# WT_ControlBoardV2.net
KiCad netlist of a schematic drawn in EAGLE
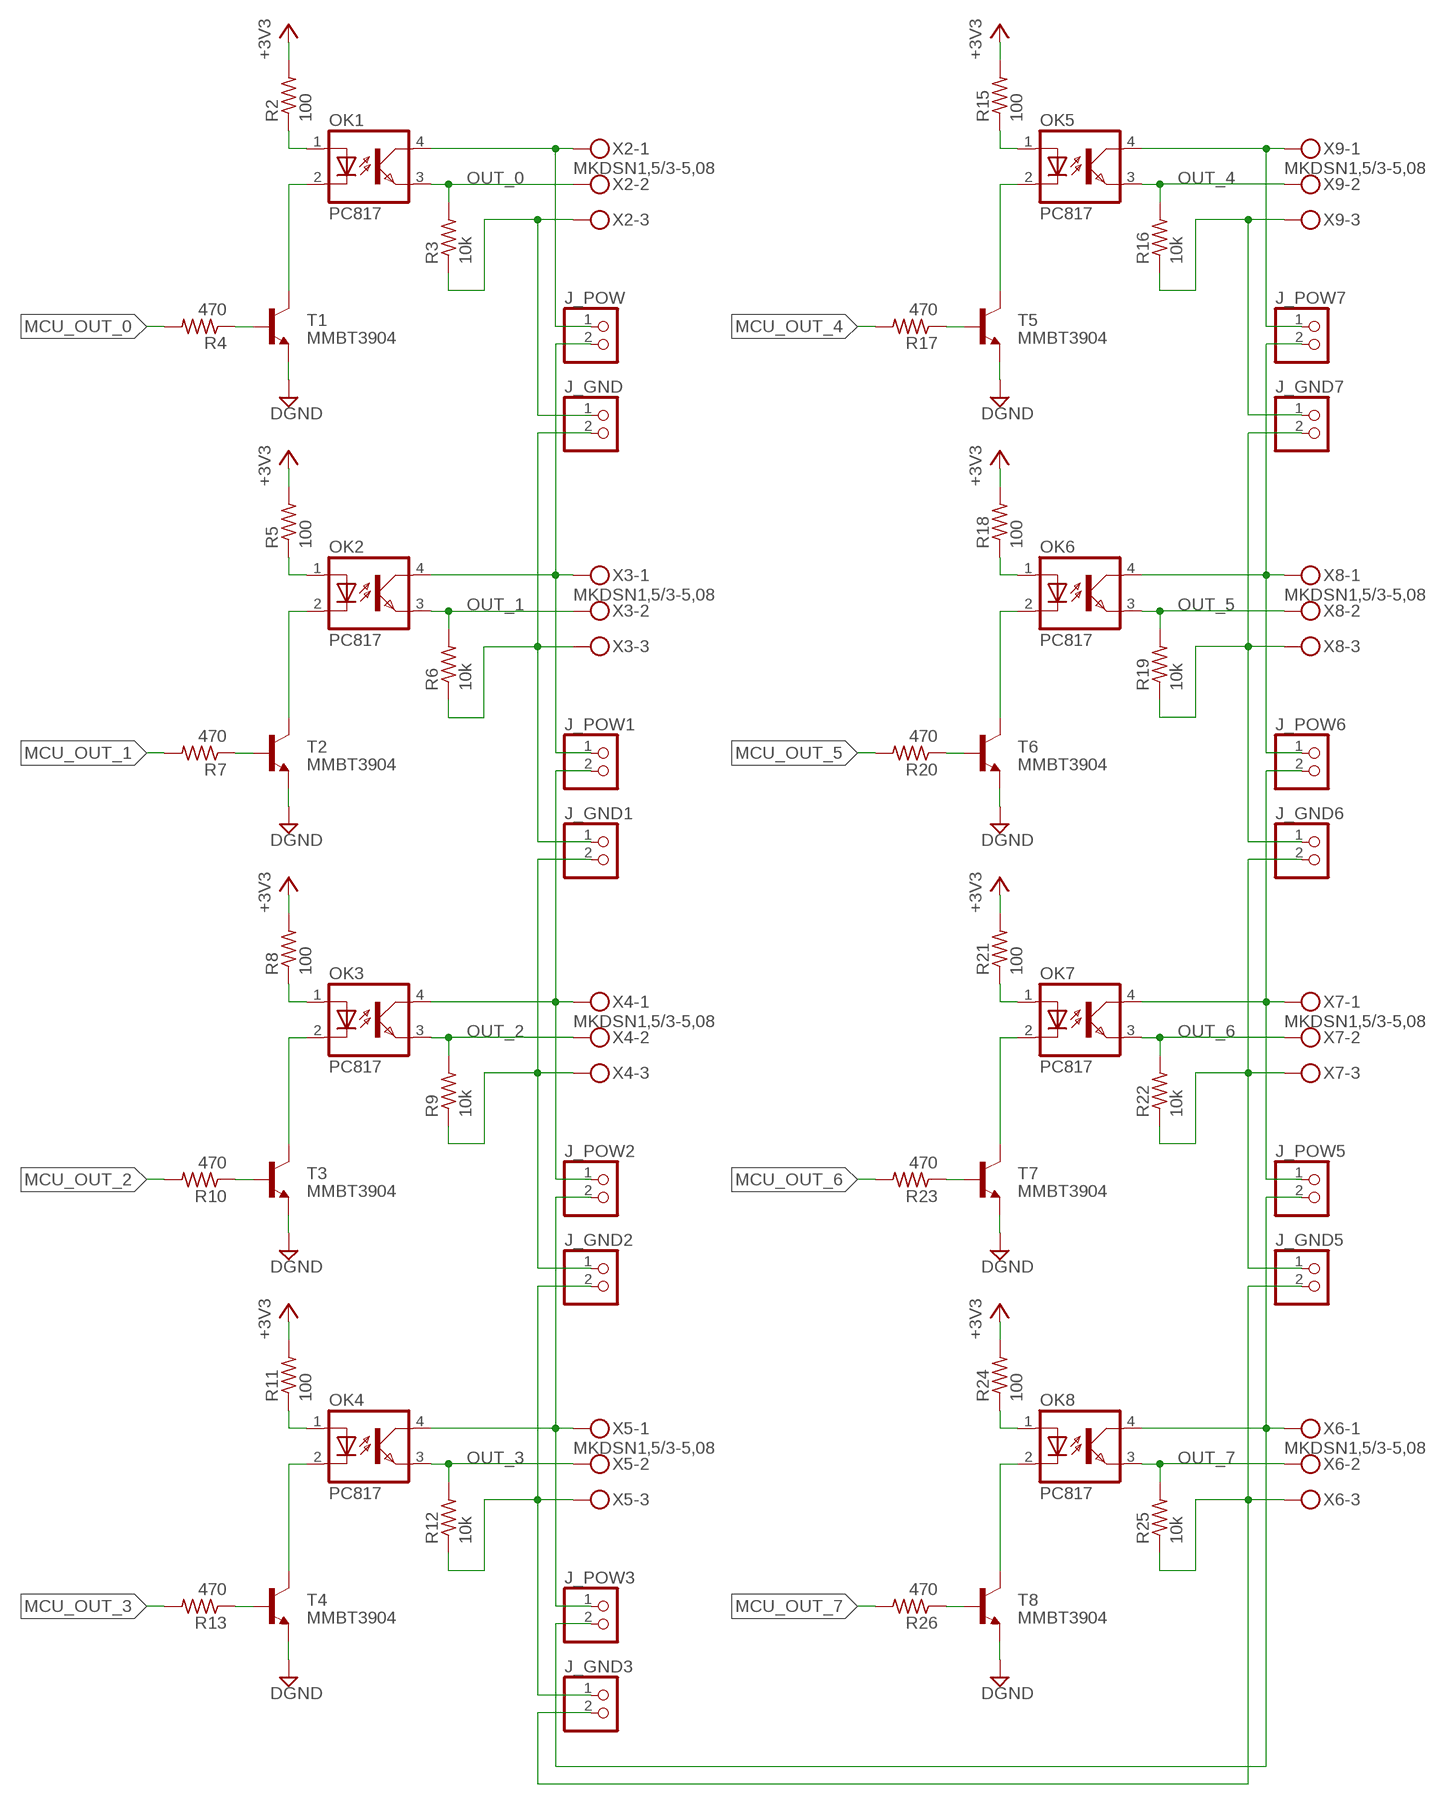
[diagram p0: schematic, sheet 1]
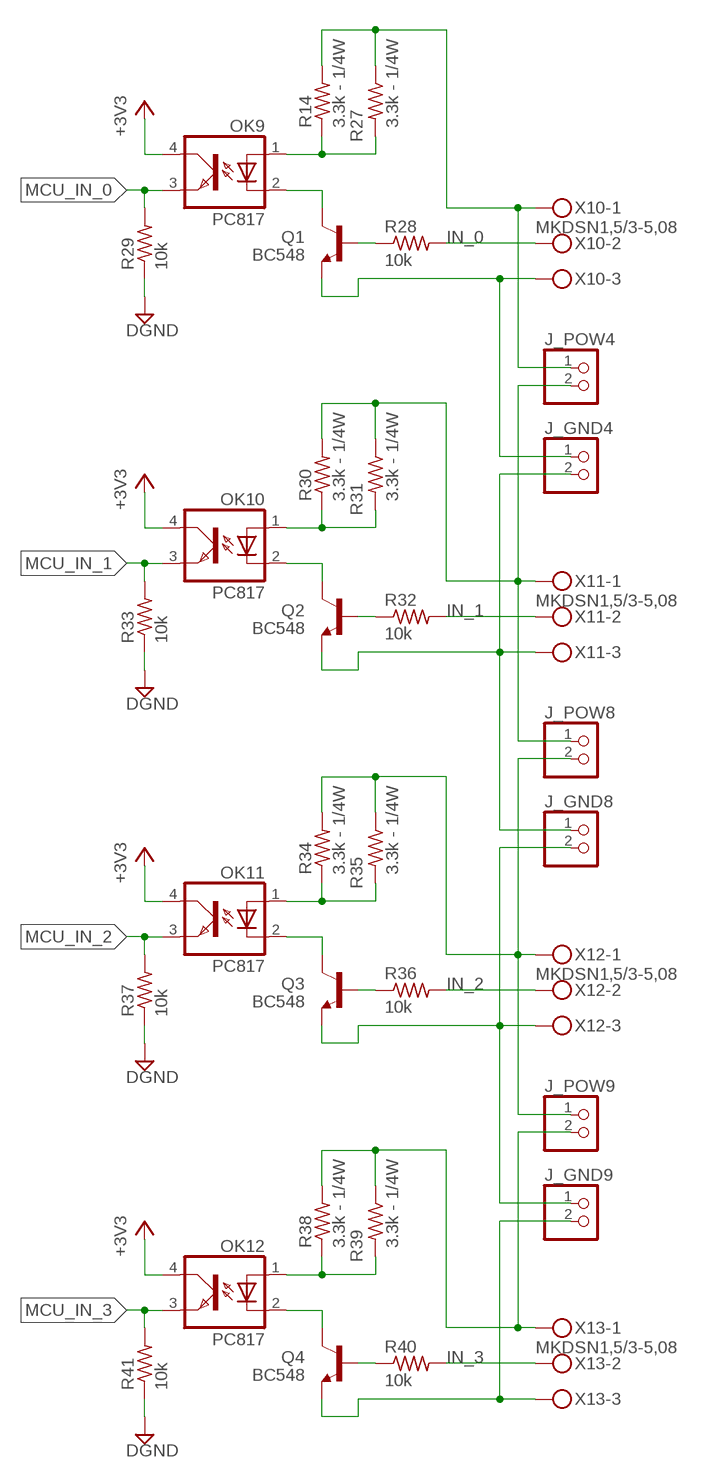
[diagram p1: schematic, sheet 2]
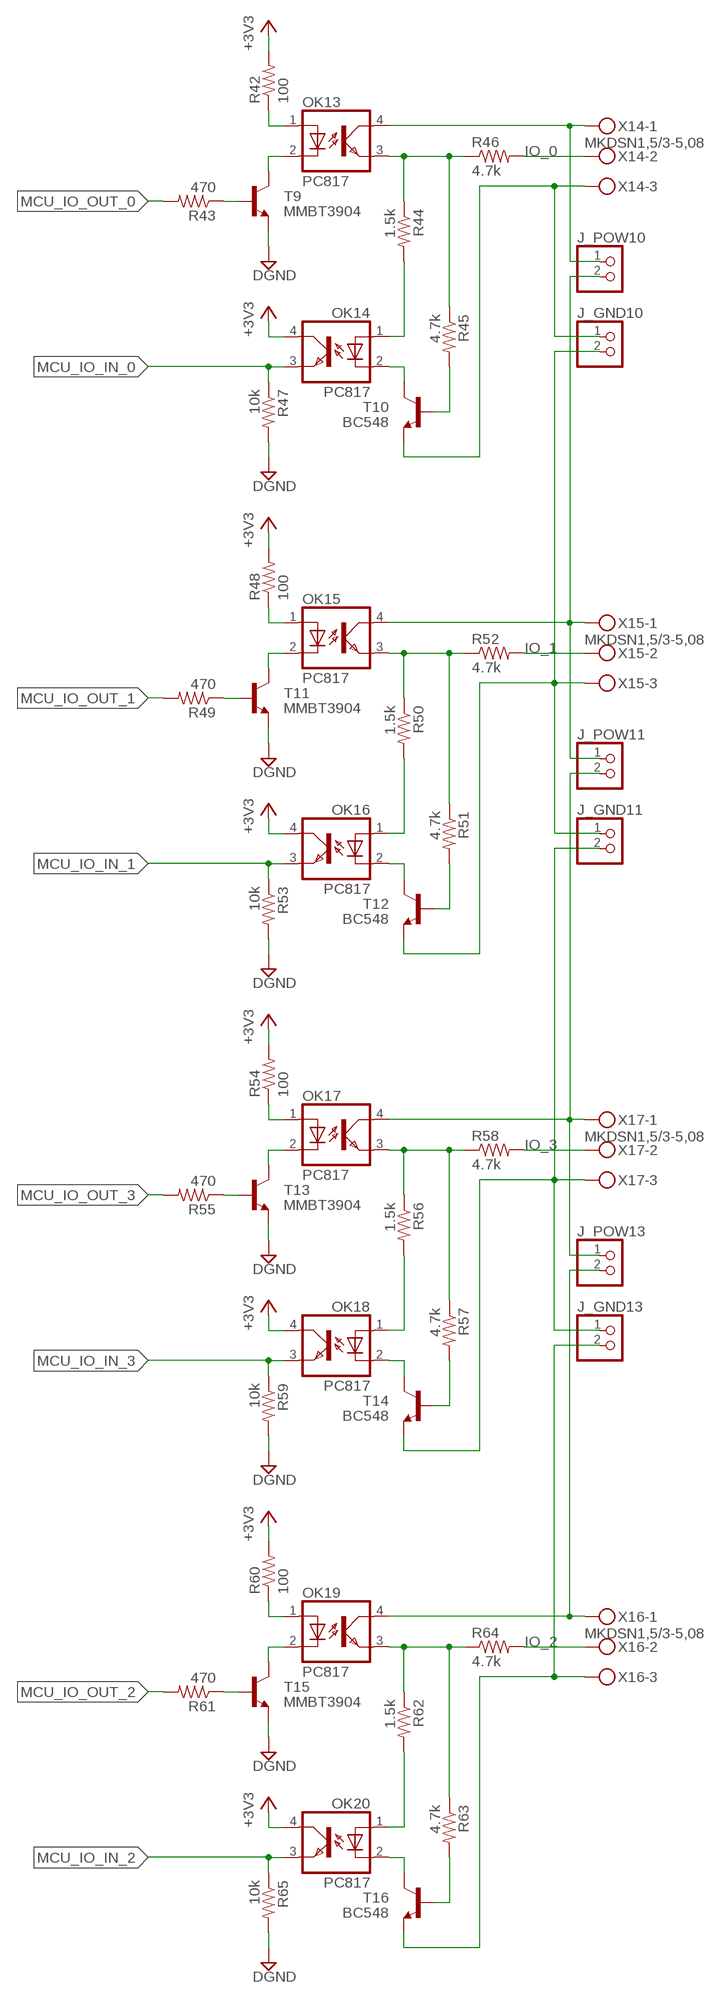
[diagram p2: schematic, sheet 3]
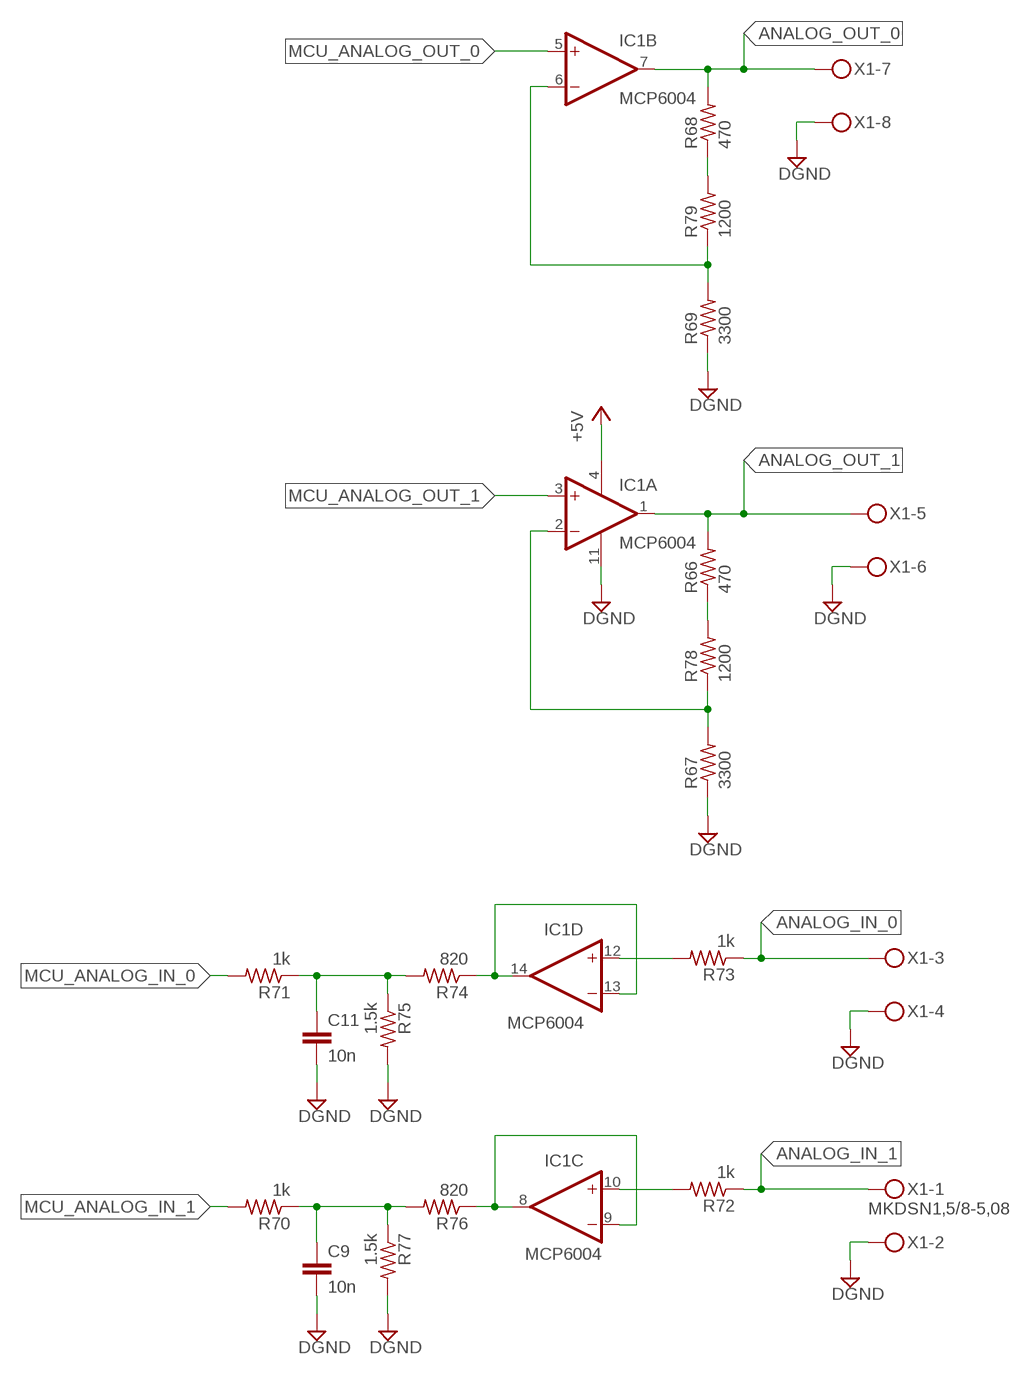
[diagram p3: schematic, sheet 4]
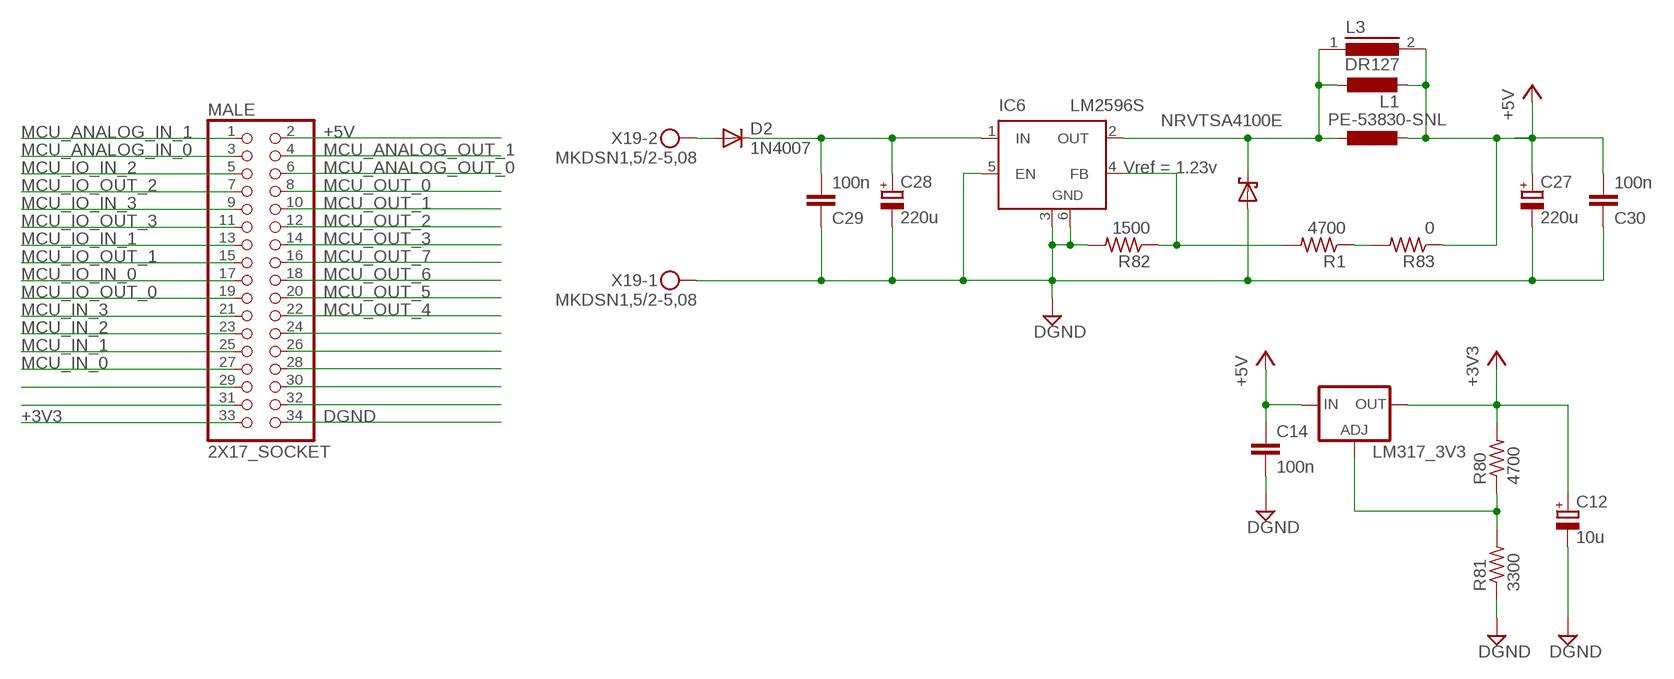
[diagram p4: schematic, sheet 5]

(export (version "E")
  (design (tool "Eeschema 10.0.6"))
  (components
    (comp (ref "J_GND4")
      (value "PINHD-1X2")
      (footprint "eagle-import:1X02")
      (libsource (lib "eagle-import") (part "PINHD-1X2"))
    )
    (comp (ref "J_GND8")
      (value "PINHD-1X2")
      (footprint "eagle-import:1X02")
      (libsource (lib "eagle-import") (part "PINHD-1X2"))
    )
    (comp (ref "J_GND9")
      (value "PINHD-1X2")
      (footprint "eagle-import:1X02")
      (libsource (lib "eagle-import") (part "PINHD-1X2"))
    )
    (comp (ref "J_POW4")
      (value "PINHD-1X2")
      (footprint "eagle-import:1X02")
      (libsource (lib "eagle-import") (part "PINHD-1X2"))
    )
    (comp (ref "J_POW8")
      (value "PINHD-1X2")
      (footprint "eagle-import:1X02")
      (libsource (lib "eagle-import") (part "PINHD-1X2"))
    )
    (comp (ref "J_POW9")
      (value "PINHD-1X2")
      (footprint "eagle-import:1X02")
      (libsource (lib "eagle-import") (part "PINHD-1X2"))
    )
    (comp (ref "OK9")
      (value "PC817")
      (footprint "eagle-import:DIL04")
      (fields (field (name "MPN") "PC817X4J000F"))
      (libsource (lib "eagle-import") (part "PC817"))
    )
    (comp (ref "OK10")
      (value "PC817")
      (footprint "eagle-import:DIL04")
      (fields (field (name "MPN") "PC817X4J000F"))
      (libsource (lib "eagle-import") (part "PC817"))
    )
    (comp (ref "OK11")
      (value "PC817")
      (footprint "eagle-import:DIL04")
      (fields (field (name "MPN") "PC817X4J000F"))
      (libsource (lib "eagle-import") (part "PC817"))
    )
    (comp (ref "OK12")
      (value "PC817")
      (footprint "eagle-import:DIL04")
      (fields (field (name "MPN") "PC817X4J000F"))
      (libsource (lib "eagle-import") (part "PC817"))
    )
    (comp (ref "Q1")
      (value "BC548")
      (footprint "eagle-import:TO92-EBC")
      (libsource (lib "eagle-import") (part "BC548"))
    )
    (comp (ref "Q2")
      (value "BC548")
      (footprint "eagle-import:TO92-EBC")
      (libsource (lib "eagle-import") (part "BC548"))
    )
    (comp (ref "Q3")
      (value "BC548")
      (footprint "eagle-import:TO92-EBC")
      (libsource (lib "eagle-import") (part "BC548"))
    )
    (comp (ref "Q4")
      (value "BC548")
      (footprint "eagle-import:TO92-EBC")
      (libsource (lib "eagle-import") (part "BC548"))
    )
    (comp (ref "R14")
      (value "3.3k - 1/4W")
      (footprint "eagle-import:0204V")
      (libsource (lib "eagle-import") (part "R-US_0204/2V"))
    )
    (comp (ref "R27")
      (value "3.3k - 1/4W")
      (footprint "eagle-import:0204V")
      (libsource (lib "eagle-import") (part "R-US_0204/2V"))
    )
    (comp (ref "R28")
      (value "10k")
      (footprint "eagle-import:0204_5")
      (libsource (lib "eagle-import") (part "R-US_0204/5"))
    )
    (comp (ref "R29")
      (value "10k")
      (footprint "eagle-import:R0402")
      (libsource (lib "eagle-import") (part "R-US_R0402"))
    )
    (comp (ref "R30")
      (value "3.3k - 1/4W")
      (footprint "eagle-import:0204V")
      (libsource (lib "eagle-import") (part "R-US_0204/2V"))
    )
    (comp (ref "R31")
      (value "3.3k - 1/4W")
      (footprint "eagle-import:0204V")
      (libsource (lib "eagle-import") (part "R-US_0204/2V"))
    )
    (comp (ref "R32")
      (value "10k")
      (footprint "eagle-import:0204_5")
      (libsource (lib "eagle-import") (part "R-US_0204/5"))
    )
    (comp (ref "R33")
      (value "10k")
      (footprint "eagle-import:R0402")
      (libsource (lib "eagle-import") (part "R-US_R0402"))
    )
    (comp (ref "R34")
      (value "3.3k - 1/4W")
      (footprint "eagle-import:0204V")
      (libsource (lib "eagle-import") (part "R-US_0204/2V"))
    )
    (comp (ref "R35")
      (value "3.3k - 1/4W")
      (footprint "eagle-import:0204V")
      (libsource (lib "eagle-import") (part "R-US_0204/2V"))
    )
    (comp (ref "R36")
      (value "10k")
      (footprint "eagle-import:0204_5")
      (libsource (lib "eagle-import") (part "R-US_0204/5"))
    )
    (comp (ref "R37")
      (value "10k")
      (footprint "eagle-import:R0402")
      (libsource (lib "eagle-import") (part "R-US_R0402"))
    )
    (comp (ref "R38")
      (value "3.3k - 1/4W")
      (footprint "eagle-import:0204V")
      (libsource (lib "eagle-import") (part "R-US_0204/2V"))
    )
    (comp (ref "R39")
      (value "3.3k - 1/4W")
      (footprint "eagle-import:0204V")
      (libsource (lib "eagle-import") (part "R-US_0204/2V"))
    )
    (comp (ref "R40")
      (value "10k")
      (footprint "eagle-import:0204_5")
      (libsource (lib "eagle-import") (part "R-US_0204/5"))
    )
    (comp (ref "R41")
      (value "10k")
      (footprint "eagle-import:R0402")
      (libsource (lib "eagle-import") (part "R-US_R0402"))
    )
    (comp (ref "X10")
      (value "MKDSN1,5/3-5,08")
      (footprint "eagle-import:MKDSN1,5_3-5,08")
      (libsource (lib "eagle-import") (part "MKDSN1,5/3-5,08"))
    )
    (comp (ref "X11")
      (value "MKDSN1,5/3-5,08")
      (footprint "eagle-import:MKDSN1,5_3-5,08")
      (libsource (lib "eagle-import") (part "MKDSN1,5/3-5,08"))
    )
    (comp (ref "X12")
      (value "MKDSN1,5/3-5,08")
      (footprint "eagle-import:MKDSN1,5_3-5,08")
      (libsource (lib "eagle-import") (part "MKDSN1,5/3-5,08"))
    )
    (comp (ref "X13")
      (value "MKDSN1,5/3-5,08")
      (footprint "eagle-import:MKDSN1,5_3-5,08")
      (libsource (lib "eagle-import") (part "MKDSN1,5/3-5,08"))
    )
    (comp (ref "J_GND10")
      (value "PINHD-1X2")
      (footprint "eagle-import:1X02")
      (libsource (lib "eagle-import") (part "PINHD-1X2"))
    )
    (comp (ref "J_GND11")
      (value "PINHD-1X2")
      (footprint "eagle-import:1X02")
      (libsource (lib "eagle-import") (part "PINHD-1X2"))
    )
    (comp (ref "J_GND13")
      (value "PINHD-1X2")
      (footprint "eagle-import:1X02")
      (libsource (lib "eagle-import") (part "PINHD-1X2"))
    )
    (comp (ref "J_POW10")
      (value "PINHD-1X2")
      (footprint "eagle-import:1X02")
      (libsource (lib "eagle-import") (part "PINHD-1X2"))
    )
    (comp (ref "J_POW11")
      (value "PINHD-1X2")
      (footprint "eagle-import:1X02")
      (libsource (lib "eagle-import") (part "PINHD-1X2"))
    )
    (comp (ref "J_POW13")
      (value "PINHD-1X2")
      (footprint "eagle-import:1X02")
      (libsource (lib "eagle-import") (part "PINHD-1X2"))
    )
    (comp (ref "OK13")
      (value "PC817")
      (footprint "eagle-import:DIL04")
      (fields (field (name "MPN") "PC817X4J000F"))
      (libsource (lib "eagle-import") (part "PC817"))
    )
    (comp (ref "OK14")
      (value "PC817")
      (footprint "eagle-import:DIL04")
      (fields (field (name "MPN") "PC817X4J000F"))
      (libsource (lib "eagle-import") (part "PC817"))
    )
    (comp (ref "OK15")
      (value "PC817")
      (footprint "eagle-import:DIL04")
      (fields (field (name "MPN") "PC817X4J000F"))
      (libsource (lib "eagle-import") (part "PC817"))
    )
    (comp (ref "OK16")
      (value "PC817")
      (footprint "eagle-import:DIL04")
      (fields (field (name "MPN") "PC817X4J000F"))
      (libsource (lib "eagle-import") (part "PC817"))
    )
    (comp (ref "OK17")
      (value "PC817")
      (footprint "eagle-import:DIL04")
      (fields (field (name "MPN") "PC817X4J000F"))
      (libsource (lib "eagle-import") (part "PC817"))
    )
    (comp (ref "OK18")
      (value "PC817")
      (footprint "eagle-import:DIL04")
      (fields (field (name "MPN") "PC817X4J000F"))
      (libsource (lib "eagle-import") (part "PC817"))
    )
    (comp (ref "OK19")
      (value "PC817")
      (footprint "eagle-import:DIL04")
      (fields (field (name "MPN") "PC817X4J000F"))
      (libsource (lib "eagle-import") (part "PC817"))
    )
    (comp (ref "OK20")
      (value "PC817")
      (footprint "eagle-import:DIL04")
      (fields (field (name "MPN") "PC817X4J000F"))
      (libsource (lib "eagle-import") (part "PC817"))
    )
    (comp (ref "R42")
      (value "100")
      (footprint "eagle-import:0204_7")
      (libsource (lib "eagle-import") (part "R-US_0204/7"))
    )
    (comp (ref "R43")
      (value "470")
      (footprint "eagle-import:R0402")
      (libsource (lib "eagle-import") (part "R-US_R0402"))
    )
    (comp (ref "R44")
      (value "1.5k")
      (footprint "eagle-import:0204_5")
      (libsource (lib "eagle-import") (part "R-US_0204/5"))
    )
    (comp (ref "R45")
      (value "4.7k")
      (footprint "eagle-import:0204V")
      (libsource (lib "eagle-import") (part "R-US_0204/2V"))
    )
    (comp (ref "R46")
      (value "4.7k")
      (footprint "eagle-import:0204V")
      (libsource (lib "eagle-import") (part "R-US_0204/2V"))
    )
    (comp (ref "R47")
      (value "10k")
      (footprint "eagle-import:0204_5")
      (libsource (lib "eagle-import") (part "R-US_0204/5"))
    )
    (comp (ref "R48")
      (value "100")
      (footprint "eagle-import:0204_7")
      (libsource (lib "eagle-import") (part "R-US_0204/7"))
    )
    (comp (ref "R49")
      (value "470")
      (footprint "eagle-import:R0402")
      (libsource (lib "eagle-import") (part "R-US_R0402"))
    )
    (comp (ref "R50")
      (value "1.5k")
      (footprint "eagle-import:0204_5")
      (libsource (lib "eagle-import") (part "R-US_0204/5"))
    )
    (comp (ref "R51")
      (value "4.7k")
      (footprint "eagle-import:0204V")
      (libsource (lib "eagle-import") (part "R-US_0204/2V"))
    )
    (comp (ref "R52")
      (value "4.7k")
      (footprint "eagle-import:0204V")
      (libsource (lib "eagle-import") (part "R-US_0204/2V"))
    )
    (comp (ref "R53")
      (value "10k")
      (footprint "eagle-import:0204_5")
      (libsource (lib "eagle-import") (part "R-US_0204/5"))
    )
    (comp (ref "R54")
      (value "100")
      (footprint "eagle-import:0204_7")
      (libsource (lib "eagle-import") (part "R-US_0204/7"))
    )
    (comp (ref "R55")
      (value "470")
      (footprint "eagle-import:R0402")
      (libsource (lib "eagle-import") (part "R-US_R0402"))
    )
    (comp (ref "R56")
      (value "1.5k")
      (footprint "eagle-import:0204_5")
      (libsource (lib "eagle-import") (part "R-US_0204/5"))
    )
    (comp (ref "R57")
      (value "4.7k")
      (footprint "eagle-import:0204V")
      (libsource (lib "eagle-import") (part "R-US_0204/2V"))
    )
    (comp (ref "R58")
      (value "4.7k")
      (footprint "eagle-import:0204V")
      (libsource (lib "eagle-import") (part "R-US_0204/2V"))
    )
    (comp (ref "R59")
      (value "10k")
      (footprint "eagle-import:0204_5")
      (libsource (lib "eagle-import") (part "R-US_0204/5"))
    )
    (comp (ref "R60")
      (value "100")
      (footprint "eagle-import:0204_7")
      (libsource (lib "eagle-import") (part "R-US_0204/7"))
    )
    (comp (ref "R61")
      (value "470")
      (footprint "eagle-import:R0402")
      (libsource (lib "eagle-import") (part "R-US_R0402"))
    )
    (comp (ref "R62")
      (value "1.5k")
      (footprint "eagle-import:0204_5")
      (libsource (lib "eagle-import") (part "R-US_0204/5"))
    )
    (comp (ref "R63")
      (value "4.7k")
      (footprint "eagle-import:0204V")
      (libsource (lib "eagle-import") (part "R-US_0204/2V"))
    )
    (comp (ref "R64")
      (value "4.7k")
      (footprint "eagle-import:0204V")
      (libsource (lib "eagle-import") (part "R-US_0204/2V"))
    )
    (comp (ref "R65")
      (value "10k")
      (footprint "eagle-import:0204_5")
      (libsource (lib "eagle-import") (part "R-US_0204/5"))
    )
    (comp (ref "T9")
      (value "MMBT3904")
      (footprint "eagle-import:SOT23-BEC")
      (libsource (lib "eagle-import") (part "-NPN-SOT23-BECMMBT3904LT1"))
    )
    (comp (ref "T10")
      (value "BC548")
      (footprint "eagle-import:TO92-CBE")
      (libsource (lib "eagle-import") (part "-NPN-TO92-CBEBC548"))
    )
    (comp (ref "T11")
      (value "MMBT3904")
      (footprint "eagle-import:SOT23-BEC")
      (libsource (lib "eagle-import") (part "-NPN-SOT23-BECMMBT3904LT1"))
    )
    (comp (ref "T12")
      (value "BC548")
      (footprint "eagle-import:TO92-CBE")
      (libsource (lib "eagle-import") (part "-NPN-TO92-CBEBC548"))
    )
    (comp (ref "T13")
      (value "MMBT3904")
      (footprint "eagle-import:SOT23-BEC")
      (libsource (lib "eagle-import") (part "-NPN-SOT23-BECMMBT3904LT1"))
    )
    (comp (ref "T14")
      (value "BC548")
      (footprint "eagle-import:TO92-CBE")
      (libsource (lib "eagle-import") (part "-NPN-TO92-CBEBC548"))
    )
    (comp (ref "T15")
      (value "MMBT3904")
      (footprint "eagle-import:SOT23-BEC")
      (libsource (lib "eagle-import") (part "-NPN-SOT23-BECMMBT3904LT1"))
    )
    (comp (ref "T16")
      (value "BC548")
      (footprint "eagle-import:TO92-CBE")
      (libsource (lib "eagle-import") (part "-NPN-TO92-CBEBC548"))
    )
    (comp (ref "X14")
      (value "MKDSN1,5/3-5,08")
      (footprint "eagle-import:MKDSN1,5_3-5,08")
      (libsource (lib "eagle-import") (part "MKDSN1,5/3-5,08"))
    )
    (comp (ref "X15")
      (value "MKDSN1,5/3-5,08")
      (footprint "eagle-import:MKDSN1,5_3-5,08")
      (libsource (lib "eagle-import") (part "MKDSN1,5/3-5,08"))
    )
    (comp (ref "X16")
      (value "MKDSN1,5/3-5,08")
      (footprint "eagle-import:MKDSN1,5_3-5,08")
      (libsource (lib "eagle-import") (part "MKDSN1,5/3-5,08"))
    )
    (comp (ref "X17")
      (value "MKDSN1,5/3-5,08")
      (footprint "eagle-import:MKDSN1,5_3-5,08")
      (libsource (lib "eagle-import") (part "MKDSN1,5/3-5,08"))
    )
    (comp (ref "C12")
      (value "10u")
      (footprint "eagle-import:E1,8-4")
      (libsource (lib "eagle-import") (part "CPOL-EUE1.8-4"))
    )
    (comp (ref "C14")
      (value "100n")
      (footprint "eagle-import:C1206")
      (libsource (lib "eagle-import") (part "C-EUC1206"))
    )
    (comp (ref "C27")
      (value "220u")
      (footprint "eagle-import:E5-10,5")
      (libsource (lib "eagle-import") (part "CPOL-EUE5-10.5"))
    )
    (comp (ref "C28")
      (value "220u")
      (footprint "eagle-import:E5-10,5")
      (libsource (lib "eagle-import") (part "CPOL-EUE5-10.5"))
    )
    (comp (ref "C29")
      (value "100n")
      (footprint "eagle-import:C1206")
      (libsource (lib "eagle-import") (part "C-EUC1206"))
    )
    (comp (ref "C30")
      (value "100n")
      (footprint "eagle-import:C1206")
      (libsource (lib "eagle-import") (part "C-EUC1206"))
    )
    (comp (ref "D2")
      (value "1N4007")
      (footprint "eagle-import:C1702-05")
      (libsource (lib "eagle-import") (part "DIODE-C1702-05"))
    )
    (comp (ref "D8")
      (value "NRVTSA4100E")
      (footprint "eagle-import:SMA-2")
      (libsource (lib "eagle-import") (part "NRVTSA4100E"))
    )
    (comp (ref "IC6")
      (value "LM2596S")
      (footprint "eagle-import:TO263-5")
      (libsource (lib "eagle-import") (part "LM2596S"))
    )
    (comp (ref "L1")
      (value "L-EUPIS2816")
      (footprint "eagle-import:PIS2816")
      (libsource (lib "eagle-import") (part "L-EUPIS2816"))
    )
    (comp (ref "L2")
      (value "PE-53830-SNL")
      (footprint "eagle-import:LCI-44")
      (libsource (lib "eagle-import") (part "PE-53830-SNL"))
    )
    (comp (ref "L3")
      (value "DR127")
      (footprint "eagle-import:DR127")
      (libsource (lib "eagle-import") (part "DR127"))
    )
    (comp (ref "LM317_3V3")
      (value "LM317TS")
      (footprint "eagle-import:317TS")
      (libsource (lib "eagle-import") (part "LM317TS"))
    )
    (comp (ref "MALE")
      (value "2X17_SOCKET")
      (footprint "eagle-import:2X17_SOCKET")
      (libsource (lib "eagle-import") (part "2X17_SOCKET"))
    )
    (comp (ref "R1")
      (value "4700")
      (footprint "eagle-import:R0402")
      (libsource (lib "eagle-import") (part "R-US_R0402"))
    )
    (comp (ref "R80")
      (value "4700")
      (footprint "eagle-import:0204V")
      (libsource (lib "eagle-import") (part "R-US_0204/2V"))
    )
    (comp (ref "R81")
      (value "3300")
      (footprint "eagle-import:0204V")
      (libsource (lib "eagle-import") (part "R-US_0204/2V"))
    )
    (comp (ref "R82")
      (value "1500")
      (footprint "eagle-import:R0402")
      (libsource (lib "eagle-import") (part "R-US_R0402"))
    )
    (comp (ref "R83")
      (value "0")
      (footprint "eagle-import:R0402")
      (libsource (lib "eagle-import") (part "R-US_R0402"))
    )
    (comp (ref "X19")
      (value "MKDSN1,5/2-5,08")
      (footprint "eagle-import:MKDSN1,5_2-5,08")
      (libsource (lib "eagle-import") (part "MKDSN1,5/2-5,08"))
    )
    (comp (ref "J_GND")
      (value "PINHD-1X2")
      (footprint "eagle-import:1X02")
      (libsource (lib "eagle-import") (part "PINHD-1X2"))
    )
    (comp (ref "J_GND1")
      (value "PINHD-1X2")
      (footprint "eagle-import:1X02")
      (libsource (lib "eagle-import") (part "PINHD-1X2"))
    )
    (comp (ref "J_GND2")
      (value "PINHD-1X2")
      (footprint "eagle-import:1X02")
      (libsource (lib "eagle-import") (part "PINHD-1X2"))
    )
    (comp (ref "J_GND3")
      (value "PINHD-1X2")
      (footprint "eagle-import:1X02")
      (libsource (lib "eagle-import") (part "PINHD-1X2"))
    )
    (comp (ref "J_GND5")
      (value "PINHD-1X2")
      (footprint "eagle-import:1X02")
      (libsource (lib "eagle-import") (part "PINHD-1X2"))
    )
    (comp (ref "J_GND6")
      (value "PINHD-1X2")
      (footprint "eagle-import:1X02")
      (libsource (lib "eagle-import") (part "PINHD-1X2"))
    )
    (comp (ref "J_GND7")
      (value "PINHD-1X2")
      (footprint "eagle-import:1X02")
      (libsource (lib "eagle-import") (part "PINHD-1X2"))
    )
    (comp (ref "J_POW")
      (value "PINHD-1X2")
      (footprint "eagle-import:1X02")
      (libsource (lib "eagle-import") (part "PINHD-1X2"))
    )
    (comp (ref "J_POW1")
      (value "PINHD-1X2")
      (footprint "eagle-import:1X02")
      (libsource (lib "eagle-import") (part "PINHD-1X2"))
    )
    (comp (ref "J_POW2")
      (value "PINHD-1X2")
      (footprint "eagle-import:1X02")
      (libsource (lib "eagle-import") (part "PINHD-1X2"))
    )
    (comp (ref "J_POW3")
      (value "PINHD-1X2")
      (footprint "eagle-import:1X02")
      (libsource (lib "eagle-import") (part "PINHD-1X2"))
    )
    (comp (ref "J_POW5")
      (value "PINHD-1X2")
      (footprint "eagle-import:1X02")
      (libsource (lib "eagle-import") (part "PINHD-1X2"))
    )
    (comp (ref "J_POW6")
      (value "PINHD-1X2")
      (footprint "eagle-import:1X02")
      (libsource (lib "eagle-import") (part "PINHD-1X2"))
    )
    (comp (ref "J_POW7")
      (value "PINHD-1X2")
      (footprint "eagle-import:1X02")
      (libsource (lib "eagle-import") (part "PINHD-1X2"))
    )
    (comp (ref "OK1")
      (value "PC817")
      (footprint "eagle-import:DIL04")
      (fields (field (name "MPN") "PC817X4J000F"))
      (libsource (lib "eagle-import") (part "PC817"))
    )
    (comp (ref "OK2")
      (value "PC817")
      (footprint "eagle-import:DIL04")
      (fields (field (name "MPN") "PC817X4J000F"))
      (libsource (lib "eagle-import") (part "PC817"))
    )
    (comp (ref "OK3")
      (value "PC817")
      (footprint "eagle-import:DIL04")
      (fields (field (name "MPN") "PC817X4J000F"))
      (libsource (lib "eagle-import") (part "PC817"))
    )
    (comp (ref "OK4")
      (value "PC817")
      (footprint "eagle-import:DIL04")
      (fields (field (name "MPN") "PC817X4J000F"))
      (libsource (lib "eagle-import") (part "PC817"))
    )
    (comp (ref "OK5")
      (value "PC817")
      (footprint "eagle-import:DIL04")
      (fields (field (name "MPN") "PC817X4J000F"))
      (libsource (lib "eagle-import") (part "PC817"))
    )
    (comp (ref "OK6")
      (value "PC817")
      (footprint "eagle-import:DIL04")
      (fields (field (name "MPN") "PC817X4J000F"))
      (libsource (lib "eagle-import") (part "PC817"))
    )
    (comp (ref "OK7")
      (value "PC817")
      (footprint "eagle-import:DIL04")
      (fields (field (name "MPN") "PC817X4J000F"))
      (libsource (lib "eagle-import") (part "PC817"))
    )
    (comp (ref "OK8")
      (value "PC817")
      (footprint "eagle-import:DIL04")
      (fields (field (name "MPN") "PC817X4J000F"))
      (libsource (lib "eagle-import") (part "PC817"))
    )
    (comp (ref "R2")
      (value "100")
      (footprint "eagle-import:R0402")
      (libsource (lib "eagle-import") (part "R-US_R0402"))
    )
    (comp (ref "R3")
      (value "10k")
      (footprint "eagle-import:R0402")
      (libsource (lib "eagle-import") (part "R-US_R0402"))
    )
    (comp (ref "R4")
      (value "470")
      (footprint "eagle-import:0204_5")
      (libsource (lib "eagle-import") (part "R-US_0204/5"))
    )
    (comp (ref "R5")
      (value "100")
      (footprint "eagle-import:R0402")
      (libsource (lib "eagle-import") (part "R-US_R0402"))
    )
    (comp (ref "R6")
      (value "10k")
      (footprint "eagle-import:R0402")
      (libsource (lib "eagle-import") (part "R-US_R0402"))
    )
    (comp (ref "R7")
      (value "470")
      (footprint "eagle-import:0204_5")
      (libsource (lib "eagle-import") (part "R-US_0204/5"))
    )
    (comp (ref "R8")
      (value "100")
      (footprint "eagle-import:R0402")
      (libsource (lib "eagle-import") (part "R-US_R0402"))
    )
    (comp (ref "R9")
      (value "10k")
      (footprint "eagle-import:R0402")
      (libsource (lib "eagle-import") (part "R-US_R0402"))
    )
    (comp (ref "R10")
      (value "470")
      (footprint "eagle-import:0204_5")
      (libsource (lib "eagle-import") (part "R-US_0204/5"))
    )
    (comp (ref "R11")
      (value "100")
      (footprint "eagle-import:R0402")
      (libsource (lib "eagle-import") (part "R-US_R0402"))
    )
    (comp (ref "R12")
      (value "10k")
      (footprint "eagle-import:R0402")
      (libsource (lib "eagle-import") (part "R-US_R0402"))
    )
    (comp (ref "R13")
      (value "470")
      (footprint "eagle-import:0204_5")
      (libsource (lib "eagle-import") (part "R-US_0204/5"))
    )
    (comp (ref "R15")
      (value "100")
      (footprint "eagle-import:R0402")
      (libsource (lib "eagle-import") (part "R-US_R0402"))
    )
    (comp (ref "R16")
      (value "10k")
      (footprint "eagle-import:R0402")
      (libsource (lib "eagle-import") (part "R-US_R0402"))
    )
    (comp (ref "R17")
      (value "470")
      (footprint "eagle-import:0204_7")
      (libsource (lib "eagle-import") (part "R-US_0204/7"))
    )
    (comp (ref "R18")
      (value "100")
      (footprint "eagle-import:R0402")
      (libsource (lib "eagle-import") (part "R-US_R0402"))
    )
    (comp (ref "R19")
      (value "10k")
      (footprint "eagle-import:R0402")
      (libsource (lib "eagle-import") (part "R-US_R0402"))
    )
    (comp (ref "R20")
      (value "470")
      (footprint "eagle-import:0204_5")
      (libsource (lib "eagle-import") (part "R-US_0204/5"))
    )
    (comp (ref "R21")
      (value "100")
      (footprint "eagle-import:R0402")
      (libsource (lib "eagle-import") (part "R-US_R0402"))
    )
    (comp (ref "R22")
      (value "10k")
      (footprint "eagle-import:R0402")
      (libsource (lib "eagle-import") (part "R-US_R0402"))
    )
    (comp (ref "R23")
      (value "470")
      (footprint "eagle-import:0204_5")
      (libsource (lib "eagle-import") (part "R-US_0204/5"))
    )
    (comp (ref "R24")
      (value "100")
      (footprint "eagle-import:R0402")
      (libsource (lib "eagle-import") (part "R-US_R0402"))
    )
    (comp (ref "R25")
      (value "10k")
      (footprint "eagle-import:R0402")
      (libsource (lib "eagle-import") (part "R-US_R0402"))
    )
    (comp (ref "R26")
      (value "470")
      (footprint "eagle-import:0204_5")
      (libsource (lib "eagle-import") (part "R-US_0204/5"))
    )
    (comp (ref "T1")
      (value "MMBT3904")
      (footprint "eagle-import:SOT23-BEC")
      (libsource (lib "eagle-import") (part "-NPN-SOT23-BECMMBT3904LT1"))
    )
    (comp (ref "T2")
      (value "MMBT3904")
      (footprint "eagle-import:SOT23-BEC")
      (libsource (lib "eagle-import") (part "-NPN-SOT23-BECMMBT3904LT1"))
    )
    (comp (ref "T3")
      (value "MMBT3904")
      (footprint "eagle-import:SOT23-BEC")
      (libsource (lib "eagle-import") (part "-NPN-SOT23-BECMMBT3904LT1"))
    )
    (comp (ref "T4")
      (value "MMBT3904")
      (footprint "eagle-import:SOT23-BEC")
      (libsource (lib "eagle-import") (part "-NPN-SOT23-BECMMBT3904LT1"))
    )
    (comp (ref "T5")
      (value "MMBT3904")
      (footprint "eagle-import:SOT23-BEC")
      (libsource (lib "eagle-import") (part "-NPN-SOT23-BECMMBT3904LT1"))
    )
    (comp (ref "T6")
      (value "MMBT3904")
      (footprint "eagle-import:SOT23-BEC")
      (libsource (lib "eagle-import") (part "-NPN-SOT23-BECMMBT3904LT1"))
    )
    (comp (ref "T7")
      (value "MMBT3904")
      (footprint "eagle-import:SOT23-BEC")
      (libsource (lib "eagle-import") (part "-NPN-SOT23-BECMMBT3904LT1"))
    )
    (comp (ref "T8")
      (value "MMBT3904")
      (footprint "eagle-import:SOT23-BEC")
      (libsource (lib "eagle-import") (part "-NPN-SOT23-BECMMBT3904LT1"))
    )
    (comp (ref "X2")
      (value "MKDSN1,5/3-5,08")
      (footprint "eagle-import:MKDSN1,5_3-5,08")
      (libsource (lib "eagle-import") (part "MKDSN1,5/3-5,08"))
    )
    (comp (ref "X3")
      (value "MKDSN1,5/3-5,08")
      (footprint "eagle-import:MKDSN1,5_3-5,08")
      (libsource (lib "eagle-import") (part "MKDSN1,5/3-5,08"))
    )
    (comp (ref "X4")
      (value "MKDSN1,5/3-5,08")
      (footprint "eagle-import:MKDSN1,5_3-5,08")
      (libsource (lib "eagle-import") (part "MKDSN1,5/3-5,08"))
    )
    (comp (ref "X5")
      (value "MKDSN1,5/3-5,08")
      (footprint "eagle-import:MKDSN1,5_3-5,08")
      (libsource (lib "eagle-import") (part "MKDSN1,5/3-5,08"))
    )
    (comp (ref "X6")
      (value "MKDSN1,5/3-5,08")
      (footprint "eagle-import:MKDSN1,5_3-5,08")
      (libsource (lib "eagle-import") (part "MKDSN1,5/3-5,08"))
    )
    (comp (ref "X7")
      (value "MKDSN1,5/3-5,08")
      (footprint "eagle-import:MKDSN1,5_3-5,08")
      (libsource (lib "eagle-import") (part "MKDSN1,5/3-5,08"))
    )
    (comp (ref "X8")
      (value "MKDSN1,5/3-5,08")
      (footprint "eagle-import:MKDSN1,5_3-5,08")
      (libsource (lib "eagle-import") (part "MKDSN1,5/3-5,08"))
    )
    (comp (ref "X9")
      (value "MKDSN1,5/3-5,08")
      (footprint "eagle-import:MKDSN1,5_3-5,08")
      (libsource (lib "eagle-import") (part "MKDSN1,5/3-5,08"))
    )
    (comp (ref "C9")
      (value "10n")
      (footprint "eagle-import:C0402")
      (libsource (lib "eagle-import") (part "C-EUC0402"))
    )
    (comp (ref "C11")
      (value "10n")
      (footprint "eagle-import:C0402")
      (libsource (lib "eagle-import") (part "C-EUC0402"))
    )
    (comp (ref "IC1")
      (value "MCP6004")
      (footprint "eagle-import:SO14")
      (libsource (lib "eagle-import") (part "LM324D"))
    )
    (comp (ref "R66")
      (value "470")
      (footprint "eagle-import:R0402")
      (libsource (lib "eagle-import") (part "R-US_R0402"))
    )
    (comp (ref "R67")
      (value "3300")
      (footprint "eagle-import:R0402")
      (libsource (lib "eagle-import") (part "R-US_R0402"))
    )
    (comp (ref "R68")
      (value "470")
      (footprint "eagle-import:R0402")
      (libsource (lib "eagle-import") (part "R-US_R0402"))
    )
    (comp (ref "R69")
      (value "3300")
      (footprint "eagle-import:R0402")
      (libsource (lib "eagle-import") (part "R-US_R0402"))
    )
    (comp (ref "R70")
      (value "1k")
      (footprint "eagle-import:R0402")
      (libsource (lib "eagle-import") (part "R-US_R0402"))
    )
    (comp (ref "R71")
      (value "1k")
      (footprint "eagle-import:R0402")
      (libsource (lib "eagle-import") (part "R-US_R0402"))
    )
    (comp (ref "R72")
      (value "1k")
      (footprint "eagle-import:0204V")
      (libsource (lib "eagle-import") (part "R-US_0204/2V"))
    )
    (comp (ref "R73")
      (value "1k")
      (footprint "eagle-import:0204_7")
      (libsource (lib "eagle-import") (part "R-US_0204/7"))
    )
    (comp (ref "R74")
      (value "820")
      (footprint "eagle-import:R0402")
      (libsource (lib "eagle-import") (part "R-US_R0402"))
    )
    (comp (ref "R75")
      (value "1.5k")
      (footprint "eagle-import:R0402")
      (libsource (lib "eagle-import") (part "R-US_R0402"))
    )
    (comp (ref "R76")
      (value "820")
      (footprint "eagle-import:R0402")
      (libsource (lib "eagle-import") (part "R-US_R0402"))
    )
    (comp (ref "R77")
      (value "1.5k")
      (footprint "eagle-import:R0402")
      (libsource (lib "eagle-import") (part "R-US_R0402"))
    )
    (comp (ref "R78")
      (value "1200")
      (footprint "eagle-import:R0402")
      (libsource (lib "eagle-import") (part "R-US_R0402"))
    )
    (comp (ref "R79")
      (value "1200")
      (footprint "eagle-import:R0402")
      (libsource (lib "eagle-import") (part "R-US_R0402"))
    )
    (comp (ref "X1")
      (value "MKDSN1,5/8-5,08")
      (footprint "eagle-import:MKDSN1,5_8-5,08")
      (libsource (lib "eagle-import") (part "MKDSN1,5/8-5,08"))
    )
  )
  (nets
    (net (code "1") (name "+3V3") (class "Default")
      (node (ref "C12") (pin "+") (pinfunction "+_+") (pintype "passive"))
      (node (ref "LM317_3V3") (pin "2") (pinfunction "OUT_2") (pintype "passive"))
      (node (ref "MALE") (pin "33") (pinfunction "33_33") (pintype "passive"))
      (node (ref "OK10") (pin "4") (pinfunction "COL_4") (pintype "passive"))
      (node (ref "OK11") (pin "4") (pinfunction "COL_4") (pintype "passive"))
      (node (ref "OK12") (pin "4") (pinfunction "COL_4") (pintype "passive"))
      (node (ref "OK14") (pin "4") (pinfunction "COL_4") (pintype "passive"))
      (node (ref "OK16") (pin "4") (pinfunction "COL_4") (pintype "passive"))
      (node (ref "OK18") (pin "4") (pinfunction "COL_4") (pintype "passive"))
      (node (ref "OK20") (pin "4") (pinfunction "COL_4") (pintype "passive"))
      (node (ref "OK9") (pin "4") (pinfunction "COL_4") (pintype "passive"))
      (node (ref "R11") (pin "2") (pinfunction "2_2") (pintype "passive"))
      (node (ref "R15") (pin "2") (pinfunction "2_2") (pintype "passive"))
      (node (ref "R18") (pin "2") (pinfunction "2_2") (pintype "passive"))
      (node (ref "R2") (pin "2") (pinfunction "2_2") (pintype "passive"))
      (node (ref "R21") (pin "2") (pinfunction "2_2") (pintype "passive"))
      (node (ref "R24") (pin "2") (pinfunction "2_2") (pintype "passive"))
      (node (ref "R42") (pin "2") (pinfunction "2_2") (pintype "passive"))
      (node (ref "R48") (pin "2") (pinfunction "2_2") (pintype "passive"))
      (node (ref "R5") (pin "2") (pinfunction "2_2") (pintype "passive"))
      (node (ref "R54") (pin "2") (pinfunction "2_2") (pintype "passive"))
      (node (ref "R60") (pin "2") (pinfunction "2_2") (pintype "passive"))
      (node (ref "R8") (pin "2") (pinfunction "2_2") (pintype "passive"))
      (node (ref "R80") (pin "2") (pinfunction "2_2") (pintype "passive"))
    )
    (net (code "2") (name "+5V") (class "Default")
      (node (ref "C14") (pin "1") (pinfunction "1_1") (pintype "passive"))
      (node (ref "C27") (pin "+") (pinfunction "+_+") (pintype "passive"))
      (node (ref "C30") (pin "2") (pinfunction "2_2") (pintype "passive"))
      (node (ref "IC1") (pin "4") (pinfunction "V+_4") (pintype "power_in"))
      (node (ref "L1") (pin "2") (pinfunction "2_2") (pintype "passive"))
      (node (ref "L2") (pin "1") (pinfunction "1_1") (pintype "passive"))
      (node (ref "L3") (pin "2") (pinfunction "2_2") (pintype "passive"))
      (node (ref "LM317_3V3") (pin "3") (pinfunction "IN_3") (pintype "input"))
      (node (ref "MALE") (pin "2") (pinfunction "2_2") (pintype "passive"))
      (node (ref "R83") (pin "1") (pinfunction "1_1") (pintype "passive"))
    )
    (net (code "3") (name "ANALOG_IN_0") (class "Default")
      (node (ref "R73") (pin "1") (pinfunction "1_1") (pintype "passive"))
      (node (ref "X1") (pin "3") (pinfunction "KL_3") (pintype "passive"))
    )
    (net (code "4") (name "ANALOG_IN_1") (class "Default")
      (node (ref "R72") (pin "1") (pinfunction "1_1") (pintype "passive"))
      (node (ref "X1") (pin "1") (pinfunction "KL_1") (pintype "passive"))
    )
    (net (code "5") (name "ANALOG_OUT_0") (class "Default")
      (node (ref "IC1") (pin "7") (pinfunction "OUT_7") (pintype "output"))
      (node (ref "R68") (pin "2") (pinfunction "2_2") (pintype "passive"))
      (node (ref "X1") (pin "7") (pinfunction "KL_7") (pintype "passive"))
    )
    (net (code "6") (name "ANALOG_OUT_1") (class "Default")
      (node (ref "IC1") (pin "1") (pinfunction "OUT_1") (pintype "output"))
      (node (ref "R66") (pin "2") (pinfunction "2_2") (pintype "passive"))
      (node (ref "X1") (pin "5") (pinfunction "KL_5") (pintype "passive"))
    )
    (net (code "7") (name "DGND") (class "Default")
      (node (ref "C11") (pin "2") (pinfunction "2_2") (pintype "passive"))
      (node (ref "C12") (pin "-") (pinfunction "-_-") (pintype "passive"))
      (node (ref "C14") (pin "2") (pinfunction "2_2") (pintype "passive"))
      (node (ref "C27") (pin "-") (pinfunction "-_-") (pintype "passive"))
      (node (ref "C28") (pin "-") (pinfunction "-_-") (pintype "passive"))
      (node (ref "C29") (pin "1") (pinfunction "1_1") (pintype "passive"))
      (node (ref "C30") (pin "1") (pinfunction "1_1") (pintype "passive"))
      (node (ref "C9") (pin "2") (pinfunction "2_2") (pintype "passive"))
      (node (ref "D8") (pin "A") (pinfunction "A_A") (pintype "passive"))
      (node (ref "IC1") (pin "11") (pinfunction "V-_11") (pintype "power_in"))
      (node (ref "IC6") (pin "3") (pinfunction "GND_3") (pintype "power_in"))
      (node (ref "IC6") (pin "5") (pinfunction "EN_5") (pintype "input"))
      (node (ref "IC6") (pin "6") (pinfunction "GND_6") (pintype "power_in"))
      (node (ref "MALE") (pin "34") (pinfunction "34_34") (pintype "passive"))
      (node (ref "R29") (pin "1") (pinfunction "1_1") (pintype "passive"))
      (node (ref "R33") (pin "1") (pinfunction "1_1") (pintype "passive"))
      (node (ref "R37") (pin "1") (pinfunction "1_1") (pintype "passive"))
      (node (ref "R41") (pin "1") (pinfunction "1_1") (pintype "passive"))
      (node (ref "R47") (pin "2") (pinfunction "2_2") (pintype "passive"))
      (node (ref "R53") (pin "2") (pinfunction "2_2") (pintype "passive"))
      (node (ref "R59") (pin "2") (pinfunction "2_2") (pintype "passive"))
      (node (ref "R65") (pin "2") (pinfunction "2_2") (pintype "passive"))
      (node (ref "R67") (pin "1") (pinfunction "1_1") (pintype "passive"))
      (node (ref "R69") (pin "1") (pinfunction "1_1") (pintype "passive"))
      (node (ref "R75") (pin "2") (pinfunction "2_2") (pintype "passive"))
      (node (ref "R77") (pin "2") (pinfunction "2_2") (pintype "passive"))
      (node (ref "R81") (pin "1") (pinfunction "1_1") (pintype "passive"))
      (node (ref "R82") (pin "2") (pinfunction "2_2") (pintype "passive"))
      (node (ref "T1") (pin "E") (pinfunction "E_E") (pintype "passive"))
      (node (ref "T11") (pin "E") (pinfunction "E_E") (pintype "passive"))
      (node (ref "T13") (pin "E") (pinfunction "E_E") (pintype "passive"))
      (node (ref "T15") (pin "E") (pinfunction "E_E") (pintype "passive"))
      (node (ref "T2") (pin "E") (pinfunction "E_E") (pintype "passive"))
      (node (ref "T3") (pin "E") (pinfunction "E_E") (pintype "passive"))
      (node (ref "T4") (pin "E") (pinfunction "E_E") (pintype "passive"))
      (node (ref "T5") (pin "E") (pinfunction "E_E") (pintype "passive"))
      (node (ref "T6") (pin "E") (pinfunction "E_E") (pintype "passive"))
      (node (ref "T7") (pin "E") (pinfunction "E_E") (pintype "passive"))
      (node (ref "T8") (pin "E") (pinfunction "E_E") (pintype "passive"))
      (node (ref "T9") (pin "E") (pinfunction "E_E") (pintype "passive"))
      (node (ref "X1") (pin "2") (pinfunction "KL_2") (pintype "passive"))
      (node (ref "X1") (pin "4") (pinfunction "KL_4") (pintype "passive"))
      (node (ref "X1") (pin "6") (pinfunction "KL_6") (pintype "passive"))
      (node (ref "X1") (pin "8") (pinfunction "KL_8") (pintype "passive"))
      (node (ref "X19") (pin "1") (pinfunction "KL_1") (pintype "passive"))
    )
    (net (code "8") (name "IN_0") (class "Default")
      (node (ref "R28") (pin "2") (pinfunction "2_2") (pintype "passive"))
      (node (ref "X10") (pin "2") (pinfunction "KL_2") (pintype "passive"))
    )
    (net (code "9") (name "IN_1") (class "Default")
      (node (ref "R32") (pin "2") (pinfunction "2_2") (pintype "passive"))
      (node (ref "X11") (pin "2") (pinfunction "KL_2") (pintype "passive"))
    )
    (net (code "10") (name "IN_2") (class "Default")
      (node (ref "R36") (pin "2") (pinfunction "2_2") (pintype "passive"))
      (node (ref "X12") (pin "2") (pinfunction "KL_2") (pintype "passive"))
    )
    (net (code "11") (name "IN_3") (class "Default")
      (node (ref "R40") (pin "2") (pinfunction "2_2") (pintype "passive"))
      (node (ref "X13") (pin "2") (pinfunction "KL_2") (pintype "passive"))
    )
    (net (code "12") (name "IO_0") (class "Default")
      (node (ref "R46") (pin "2") (pinfunction "2_2") (pintype "passive"))
      (node (ref "X14") (pin "2") (pinfunction "KL_2") (pintype "passive"))
    )
    (net (code "13") (name "IO_1") (class "Default")
      (node (ref "R52") (pin "2") (pinfunction "2_2") (pintype "passive"))
      (node (ref "X15") (pin "2") (pinfunction "KL_2") (pintype "passive"))
    )
    (net (code "14") (name "IO_2") (class "Default")
      (node (ref "R64") (pin "2") (pinfunction "2_2") (pintype "passive"))
      (node (ref "X16") (pin "2") (pinfunction "KL_2") (pintype "passive"))
    )
    (net (code "15") (name "IO_3") (class "Default")
      (node (ref "R58") (pin "2") (pinfunction "2_2") (pintype "passive"))
      (node (ref "X17") (pin "2") (pinfunction "KL_2") (pintype "passive"))
    )
    (net (code "16") (name "MCU_ANALOG_IN_0") (class "Default")
      (node (ref "MALE") (pin "3") (pinfunction "3_3") (pintype "passive"))
      (node (ref "R71") (pin "2") (pinfunction "2_2") (pintype "passive"))
    )
    (net (code "17") (name "MCU_ANALOG_IN_1") (class "Default")
      (node (ref "MALE") (pin "1") (pinfunction "1_1") (pintype "passive"))
      (node (ref "R70") (pin "2") (pinfunction "2_2") (pintype "passive"))
    )
    (net (code "18") (name "MCU_ANALOG_OUT_0") (class "Default")
      (node (ref "IC1") (pin "5") (pinfunction "+IN_5") (pintype "input"))
      (node (ref "MALE") (pin "6") (pinfunction "6_6") (pintype "passive"))
    )
    (net (code "19") (name "MCU_ANALOG_OUT_1") (class "Default")
      (node (ref "IC1") (pin "3") (pinfunction "+IN_3") (pintype "input"))
      (node (ref "MALE") (pin "4") (pinfunction "4_4") (pintype "passive"))
    )
    (net (code "20") (name "MCU_IN_0") (class "Default")
      (node (ref "MALE") (pin "27") (pinfunction "27_27") (pintype "passive"))
      (node (ref "OK9") (pin "3") (pinfunction "EMIT_3") (pintype "passive"))
      (node (ref "R29") (pin "2") (pinfunction "2_2") (pintype "passive"))
    )
    (net (code "21") (name "MCU_IN_1") (class "Default")
      (node (ref "MALE") (pin "25") (pinfunction "25_25") (pintype "passive"))
      (node (ref "OK10") (pin "3") (pinfunction "EMIT_3") (pintype "passive"))
      (node (ref "R33") (pin "2") (pinfunction "2_2") (pintype "passive"))
    )
    (net (code "22") (name "MCU_IN_2") (class "Default")
      (node (ref "MALE") (pin "23") (pinfunction "23_23") (pintype "passive"))
      (node (ref "OK11") (pin "3") (pinfunction "EMIT_3") (pintype "passive"))
      (node (ref "R37") (pin "2") (pinfunction "2_2") (pintype "passive"))
    )
    (net (code "23") (name "MCU_IN_3") (class "Default")
      (node (ref "MALE") (pin "21") (pinfunction "21_21") (pintype "passive"))
      (node (ref "OK12") (pin "3") (pinfunction "EMIT_3") (pintype "passive"))
      (node (ref "R41") (pin "2") (pinfunction "2_2") (pintype "passive"))
    )
    (net (code "24") (name "MCU_IO_IN_0") (class "Default")
      (node (ref "MALE") (pin "17") (pinfunction "17_17") (pintype "passive"))
      (node (ref "OK14") (pin "3") (pinfunction "EMIT_3") (pintype "passive"))
      (node (ref "R47") (pin "1") (pinfunction "1_1") (pintype "passive"))
    )
    (net (code "25") (name "MCU_IO_IN_1") (class "Default")
      (node (ref "MALE") (pin "13") (pinfunction "13_13") (pintype "passive"))
      (node (ref "OK16") (pin "3") (pinfunction "EMIT_3") (pintype "passive"))
      (node (ref "R53") (pin "1") (pinfunction "1_1") (pintype "passive"))
    )
    (net (code "26") (name "MCU_IO_IN_2") (class "Default")
      (node (ref "MALE") (pin "5") (pinfunction "5_5") (pintype "passive"))
      (node (ref "OK20") (pin "3") (pinfunction "EMIT_3") (pintype "passive"))
      (node (ref "R65") (pin "1") (pinfunction "1_1") (pintype "passive"))
    )
    (net (code "27") (name "MCU_IO_IN_3") (class "Default")
      (node (ref "MALE") (pin "9") (pinfunction "9_9") (pintype "passive"))
      (node (ref "OK18") (pin "3") (pinfunction "EMIT_3") (pintype "passive"))
      (node (ref "R59") (pin "1") (pinfunction "1_1") (pintype "passive"))
    )
    (net (code "28") (name "MCU_IO_OUT_0") (class "Default")
      (node (ref "MALE") (pin "19") (pinfunction "19_19") (pintype "passive"))
      (node (ref "R43") (pin "2") (pinfunction "2_2") (pintype "passive"))
    )
    (net (code "29") (name "MCU_IO_OUT_1") (class "Default")
      (node (ref "MALE") (pin "15") (pinfunction "15_15") (pintype "passive"))
      (node (ref "R49") (pin "2") (pinfunction "2_2") (pintype "passive"))
    )
    (net (code "30") (name "MCU_IO_OUT_2") (class "Default")
      (node (ref "MALE") (pin "7") (pinfunction "7_7") (pintype "passive"))
      (node (ref "R61") (pin "2") (pinfunction "2_2") (pintype "passive"))
    )
    (net (code "31") (name "MCU_IO_OUT_3") (class "Default")
      (node (ref "MALE") (pin "11") (pinfunction "11_11") (pintype "passive"))
      (node (ref "R55") (pin "2") (pinfunction "2_2") (pintype "passive"))
    )
    (net (code "32") (name "MCU_OUT_0") (class "Default")
      (node (ref "MALE") (pin "8") (pinfunction "8_8") (pintype "passive"))
      (node (ref "R4") (pin "2") (pinfunction "2_2") (pintype "passive"))
    )
    (net (code "33") (name "MCU_OUT_1") (class "Default")
      (node (ref "MALE") (pin "10") (pinfunction "10_10") (pintype "passive"))
      (node (ref "R7") (pin "2") (pinfunction "2_2") (pintype "passive"))
    )
    (net (code "34") (name "MCU_OUT_2") (class "Default")
      (node (ref "MALE") (pin "12") (pinfunction "12_12") (pintype "passive"))
      (node (ref "R10") (pin "2") (pinfunction "2_2") (pintype "passive"))
    )
    (net (code "35") (name "MCU_OUT_3") (class "Default")
      (node (ref "MALE") (pin "14") (pinfunction "14_14") (pintype "passive"))
      (node (ref "R13") (pin "2") (pinfunction "2_2") (pintype "passive"))
    )
    (net (code "36") (name "MCU_OUT_4") (class "Default")
      (node (ref "MALE") (pin "22") (pinfunction "22_22") (pintype "passive"))
      (node (ref "R17") (pin "2") (pinfunction "2_2") (pintype "passive"))
    )
    (net (code "37") (name "MCU_OUT_5") (class "Default")
      (node (ref "MALE") (pin "20") (pinfunction "20_20") (pintype "passive"))
      (node (ref "R20") (pin "2") (pinfunction "2_2") (pintype "passive"))
    )
    (net (code "38") (name "MCU_OUT_6") (class "Default")
      (node (ref "MALE") (pin "18") (pinfunction "18_18") (pintype "passive"))
      (node (ref "R23") (pin "2") (pinfunction "2_2") (pintype "passive"))
    )
    (net (code "39") (name "MCU_OUT_7") (class "Default")
      (node (ref "MALE") (pin "16") (pinfunction "16_16") (pintype "passive"))
      (node (ref "R26") (pin "2") (pinfunction "2_2") (pintype "passive"))
    )
    (net (code "40") (name "Net-(C9-Pad1)") (class "Default")
      (node (ref "C9") (pin "1") (pinfunction "1_1") (pintype "passive"))
      (node (ref "R70") (pin "1") (pinfunction "1_1") (pintype "passive"))
      (node (ref "R76") (pin "2") (pinfunction "2_2") (pintype "passive"))
      (node (ref "R77") (pin "1") (pinfunction "1_1") (pintype "passive"))
    )
    (net (code "41") (name "Net-(C11-Pad1)") (class "Default")
      (node (ref "C11") (pin "1") (pinfunction "1_1") (pintype "passive"))
      (node (ref "R71") (pin "1") (pinfunction "1_1") (pintype "passive"))
      (node (ref "R74") (pin "2") (pinfunction "2_2") (pintype "passive"))
      (node (ref "R75") (pin "1") (pinfunction "1_1") (pintype "passive"))
    )
    (net (code "42") (name "Net-(IC1A--IN)") (class "Default")
      (node (ref "IC1") (pin "2") (pinfunction "-IN_2") (pintype "input"))
      (node (ref "R67") (pin "2") (pinfunction "2_2") (pintype "passive"))
      (node (ref "R78") (pin "1") (pinfunction "1_1") (pintype "passive"))
    )
    (net (code "43") (name "Net-(IC1B--IN)") (class "Default")
      (node (ref "IC1") (pin "6") (pinfunction "-IN_6") (pintype "input"))
      (node (ref "R69") (pin "2") (pinfunction "2_2") (pintype "passive"))
      (node (ref "R79") (pin "1") (pinfunction "1_1") (pintype "passive"))
    )
    (net (code "44") (name "Net-(IC1C-+IN)") (class "Default")
      (node (ref "IC1") (pin "10") (pinfunction "+IN_10") (pintype "input"))
      (node (ref "R72") (pin "2") (pinfunction "2_2") (pintype "passive"))
    )
    (net (code "45") (name "Net-(IC1C--IN)") (class "Default")
      (node (ref "IC1") (pin "8") (pinfunction "OUT_8") (pintype "output"))
      (node (ref "IC1") (pin "9") (pinfunction "-IN_9") (pintype "input"))
      (node (ref "R76") (pin "1") (pinfunction "1_1") (pintype "passive"))
    )
    (net (code "46") (name "Net-(IC1D-+IN)") (class "Default")
      (node (ref "IC1") (pin "12") (pinfunction "+IN_12") (pintype "input"))
      (node (ref "R73") (pin "2") (pinfunction "2_2") (pintype "passive"))
    )
    (net (code "47") (name "Net-(IC1D--IN)") (class "Default")
      (node (ref "IC1") (pin "13") (pinfunction "-IN_13") (pintype "input"))
      (node (ref "IC1") (pin "14") (pinfunction "OUT_14") (pintype "output"))
      (node (ref "R74") (pin "1") (pinfunction "1_1") (pintype "passive"))
    )
    (net (code "48") (name "Net-(IC6-FB)") (class "Default")
      (node (ref "IC6") (pin "4") (pinfunction "FB_4") (pintype "input"))
      (node (ref "R1") (pin "2") (pinfunction "2_2") (pintype "passive"))
      (node (ref "R82") (pin "1") (pinfunction "1_1") (pintype "passive"))
    )
    (net (code "49") (name "Net-(IC6-IN)") (class "Default")
      (node (ref "C28") (pin "+") (pinfunction "+_+") (pintype "passive"))
      (node (ref "C29") (pin "2") (pinfunction "2_2") (pintype "passive"))
      (node (ref "D2") (pin "C") (pinfunction "C_C") (pintype "passive"))
      (node (ref "IC6") (pin "1") (pinfunction "IN_1") (pintype "input"))
    )
    (net (code "50") (name "Net-(IC6-OUT)") (class "Default")
      (node (ref "D8") (pin "C") (pinfunction "C_C") (pintype "passive"))
      (node (ref "IC6") (pin "2") (pinfunction "OUT_2") (pintype "output"))
      (node (ref "L1") (pin "1") (pinfunction "1_1") (pintype "passive"))
      (node (ref "L2") (pin "2") (pinfunction "2_2") (pintype "passive"))
      (node (ref "L3") (pin "1") (pinfunction "1_1") (pintype "passive"))
    )
    (net (code "51") (name "Net-(LM317_3V3-ADJ)") (class "Default")
      (node (ref "LM317_3V3") (pin "1") (pinfunction "ADJ_1") (pintype "input"))
      (node (ref "R80") (pin "1") (pinfunction "1_1") (pintype "passive"))
      (node (ref "R81") (pin "2") (pinfunction "2_2") (pintype "passive"))
    )
    (net (code "52") (name "Net-(OK1-A)") (class "Default")
      (node (ref "OK1") (pin "1") (pinfunction "A_1") (pintype "passive"))
      (node (ref "R2") (pin "1") (pinfunction "1_1") (pintype "passive"))
    )
    (net (code "53") (name "Net-(OK1-C)") (class "Default")
      (node (ref "OK1") (pin "2") (pinfunction "C_2") (pintype "passive"))
      (node (ref "T1") (pin "C") (pinfunction "C_C") (pintype "passive"))
    )
    (net (code "54") (name "Net-(OK1-COL)") (class "Default")
      (node (ref "J_POW") (pin "1") (pinfunction "1_1") (pintype "passive"))
      (node (ref "OK1") (pin "4") (pinfunction "COL_4") (pintype "passive"))
      (node (ref "X2") (pin "1") (pinfunction "KL_1") (pintype "passive"))
    )
    (net (code "55") (name "Net-(OK2-A)") (class "Default")
      (node (ref "OK2") (pin "1") (pinfunction "A_1") (pintype "passive"))
      (node (ref "R5") (pin "1") (pinfunction "1_1") (pintype "passive"))
    )
    (net (code "56") (name "Net-(OK2-C)") (class "Default")
      (node (ref "OK2") (pin "2") (pinfunction "C_2") (pintype "passive"))
      (node (ref "T2") (pin "C") (pinfunction "C_C") (pintype "passive"))
    )
    (net (code "57") (name "Net-(OK2-COL)") (class "Default")
      (node (ref "J_POW") (pin "2") (pinfunction "2_2") (pintype "passive"))
      (node (ref "J_POW1") (pin "1") (pinfunction "1_1") (pintype "passive"))
      (node (ref "OK2") (pin "4") (pinfunction "COL_4") (pintype "passive"))
      (node (ref "X3") (pin "1") (pinfunction "KL_1") (pintype "passive"))
    )
    (net (code "58") (name "Net-(OK3-A)") (class "Default")
      (node (ref "OK3") (pin "1") (pinfunction "A_1") (pintype "passive"))
      (node (ref "R8") (pin "1") (pinfunction "1_1") (pintype "passive"))
    )
    (net (code "59") (name "Net-(OK3-C)") (class "Default")
      (node (ref "OK3") (pin "2") (pinfunction "C_2") (pintype "passive"))
      (node (ref "T3") (pin "C") (pinfunction "C_C") (pintype "passive"))
    )
    (net (code "60") (name "Net-(OK3-COL)") (class "Default")
      (node (ref "J_POW1") (pin "2") (pinfunction "2_2") (pintype "passive"))
      (node (ref "J_POW2") (pin "1") (pinfunction "1_1") (pintype "passive"))
      (node (ref "OK3") (pin "4") (pinfunction "COL_4") (pintype "passive"))
      (node (ref "X4") (pin "1") (pinfunction "KL_1") (pintype "passive"))
    )
    (net (code "61") (name "Net-(OK4-A)") (class "Default")
      (node (ref "OK4") (pin "1") (pinfunction "A_1") (pintype "passive"))
      (node (ref "R11") (pin "1") (pinfunction "1_1") (pintype "passive"))
    )
    (net (code "62") (name "Net-(OK4-C)") (class "Default")
      (node (ref "OK4") (pin "2") (pinfunction "C_2") (pintype "passive"))
      (node (ref "T4") (pin "C") (pinfunction "C_C") (pintype "passive"))
    )
    (net (code "63") (name "Net-(OK4-COL)") (class "Default")
      (node (ref "J_POW2") (pin "2") (pinfunction "2_2") (pintype "passive"))
      (node (ref "J_POW3") (pin "1") (pinfunction "1_1") (pintype "passive"))
      (node (ref "OK4") (pin "4") (pinfunction "COL_4") (pintype "passive"))
      (node (ref "X5") (pin "1") (pinfunction "KL_1") (pintype "passive"))
    )
    (net (code "64") (name "Net-(OK5-A)") (class "Default")
      (node (ref "OK5") (pin "1") (pinfunction "A_1") (pintype "passive"))
      (node (ref "R15") (pin "1") (pinfunction "1_1") (pintype "passive"))
    )
    (net (code "65") (name "Net-(OK5-C)") (class "Default")
      (node (ref "OK5") (pin "2") (pinfunction "C_2") (pintype "passive"))
      (node (ref "T5") (pin "C") (pinfunction "C_C") (pintype "passive"))
    )
    (net (code "66") (name "Net-(OK5-COL)") (class "Default")
      (node (ref "J_POW7") (pin "1") (pinfunction "1_1") (pintype "passive"))
      (node (ref "OK5") (pin "4") (pinfunction "COL_4") (pintype "passive"))
      (node (ref "X9") (pin "1") (pinfunction "KL_1") (pintype "passive"))
    )
    (net (code "67") (name "Net-(OK6-A)") (class "Default")
      (node (ref "OK6") (pin "1") (pinfunction "A_1") (pintype "passive"))
      (node (ref "R18") (pin "1") (pinfunction "1_1") (pintype "passive"))
    )
    (net (code "68") (name "Net-(OK6-C)") (class "Default")
      (node (ref "OK6") (pin "2") (pinfunction "C_2") (pintype "passive"))
      (node (ref "T6") (pin "C") (pinfunction "C_C") (pintype "passive"))
    )
    (net (code "69") (name "Net-(OK6-COL)") (class "Default")
      (node (ref "J_POW6") (pin "1") (pinfunction "1_1") (pintype "passive"))
      (node (ref "J_POW7") (pin "2") (pinfunction "2_2") (pintype "passive"))
      (node (ref "OK6") (pin "4") (pinfunction "COL_4") (pintype "passive"))
      (node (ref "X8") (pin "1") (pinfunction "KL_1") (pintype "passive"))
    )
    (net (code "70") (name "Net-(OK7-A)") (class "Default")
      (node (ref "OK7") (pin "1") (pinfunction "A_1") (pintype "passive"))
      (node (ref "R21") (pin "1") (pinfunction "1_1") (pintype "passive"))
    )
    (net (code "71") (name "Net-(OK7-C)") (class "Default")
      (node (ref "OK7") (pin "2") (pinfunction "C_2") (pintype "passive"))
      (node (ref "T7") (pin "C") (pinfunction "C_C") (pintype "passive"))
    )
    (net (code "72") (name "Net-(OK7-COL)") (class "Default")
      (node (ref "J_POW5") (pin "1") (pinfunction "1_1") (pintype "passive"))
      (node (ref "J_POW6") (pin "2") (pinfunction "2_2") (pintype "passive"))
      (node (ref "OK7") (pin "4") (pinfunction "COL_4") (pintype "passive"))
      (node (ref "X7") (pin "1") (pinfunction "KL_1") (pintype "passive"))
    )
    (net (code "73") (name "Net-(OK8-A)") (class "Default")
      (node (ref "OK8") (pin "1") (pinfunction "A_1") (pintype "passive"))
      (node (ref "R24") (pin "1") (pinfunction "1_1") (pintype "passive"))
    )
    (net (code "74") (name "Net-(OK8-C)") (class "Default")
      (node (ref "OK8") (pin "2") (pinfunction "C_2") (pintype "passive"))
      (node (ref "T8") (pin "C") (pinfunction "C_C") (pintype "passive"))
    )
    (net (code "75") (name "Net-(OK8-COL)") (class "Default")
      (node (ref "J_POW3") (pin "2") (pinfunction "2_2") (pintype "passive"))
      (node (ref "J_POW5") (pin "2") (pinfunction "2_2") (pintype "passive"))
      (node (ref "OK8") (pin "4") (pinfunction "COL_4") (pintype "passive"))
      (node (ref "X6") (pin "1") (pinfunction "KL_1") (pintype "passive"))
    )
    (net (code "76") (name "Net-(OK9-A)") (class "Default")
      (node (ref "OK9") (pin "1") (pinfunction "A_1") (pintype "passive"))
      (node (ref "R14") (pin "1") (pinfunction "1_1") (pintype "passive"))
      (node (ref "R27") (pin "2") (pinfunction "2_2") (pintype "passive"))
    )
    (net (code "77") (name "Net-(OK9-C)") (class "Default")
      (node (ref "OK9") (pin "2") (pinfunction "C_2") (pintype "passive"))
      (node (ref "Q1") (pin "C") (pinfunction "C_C") (pintype "passive"))
    )
    (net (code "78") (name "Net-(OK10-A)") (class "Default")
      (node (ref "OK10") (pin "1") (pinfunction "A_1") (pintype "passive"))
      (node (ref "R30") (pin "1") (pinfunction "1_1") (pintype "passive"))
      (node (ref "R31") (pin "2") (pinfunction "2_2") (pintype "passive"))
    )
    (net (code "79") (name "Net-(OK10-C)") (class "Default")
      (node (ref "OK10") (pin "2") (pinfunction "C_2") (pintype "passive"))
      (node (ref "Q2") (pin "C") (pinfunction "C_C") (pintype "passive"))
    )
    (net (code "80") (name "Net-(OK11-A)") (class "Default")
      (node (ref "OK11") (pin "1") (pinfunction "A_1") (pintype "passive"))
      (node (ref "R34") (pin "1") (pinfunction "1_1") (pintype "passive"))
      (node (ref "R35") (pin "2") (pinfunction "2_2") (pintype "passive"))
    )
    (net (code "81") (name "Net-(OK11-C)") (class "Default")
      (node (ref "OK11") (pin "2") (pinfunction "C_2") (pintype "passive"))
      (node (ref "Q3") (pin "C") (pinfunction "C_C") (pintype "passive"))
    )
    (net (code "82") (name "Net-(OK12-A)") (class "Default")
      (node (ref "OK12") (pin "1") (pinfunction "A_1") (pintype "passive"))
      (node (ref "R38") (pin "1") (pinfunction "1_1") (pintype "passive"))
      (node (ref "R39") (pin "2") (pinfunction "2_2") (pintype "passive"))
    )
    (net (code "83") (name "Net-(OK12-C)") (class "Default")
      (node (ref "OK12") (pin "2") (pinfunction "C_2") (pintype "passive"))
      (node (ref "Q4") (pin "C") (pinfunction "C_C") (pintype "passive"))
    )
    (net (code "84") (name "Net-(OK13-A)") (class "Default")
      (node (ref "OK13") (pin "1") (pinfunction "A_1") (pintype "passive"))
      (node (ref "R42") (pin "1") (pinfunction "1_1") (pintype "passive"))
    )
    (net (code "85") (name "Net-(OK13-C)") (class "Default")
      (node (ref "OK13") (pin "2") (pinfunction "C_2") (pintype "passive"))
      (node (ref "T9") (pin "C") (pinfunction "C_C") (pintype "passive"))
    )
    (net (code "86") (name "Net-(OK13-COL)") (class "Default")
      (node (ref "J_POW10") (pin "1") (pinfunction "1_1") (pintype "passive"))
      (node (ref "OK13") (pin "4") (pinfunction "COL_4") (pintype "passive"))
      (node (ref "X14") (pin "1") (pinfunction "KL_1") (pintype "passive"))
    )
    (net (code "87") (name "Net-(OK13-EMIT)") (class "Default")
      (node (ref "OK13") (pin "3") (pinfunction "EMIT_3") (pintype "passive"))
      (node (ref "R44") (pin "1") (pinfunction "1_1") (pintype "passive"))
      (node (ref "R45") (pin "1") (pinfunction "1_1") (pintype "passive"))
      (node (ref "R46") (pin "1") (pinfunction "1_1") (pintype "passive"))
    )
    (net (code "88") (name "Net-(OK14-A)") (class "Default")
      (node (ref "OK14") (pin "1") (pinfunction "A_1") (pintype "passive"))
      (node (ref "R44") (pin "2") (pinfunction "2_2") (pintype "passive"))
    )
    (net (code "89") (name "Net-(OK14-C)") (class "Default")
      (node (ref "OK14") (pin "2") (pinfunction "C_2") (pintype "passive"))
      (node (ref "T10") (pin "C") (pinfunction "C_C") (pintype "passive"))
    )
    (net (code "90") (name "Net-(OK15-A)") (class "Default")
      (node (ref "OK15") (pin "1") (pinfunction "A_1") (pintype "passive"))
      (node (ref "R48") (pin "1") (pinfunction "1_1") (pintype "passive"))
    )
    (net (code "91") (name "Net-(OK15-C)") (class "Default")
      (node (ref "OK15") (pin "2") (pinfunction "C_2") (pintype "passive"))
      (node (ref "T11") (pin "C") (pinfunction "C_C") (pintype "passive"))
    )
    (net (code "92") (name "Net-(OK15-COL)") (class "Default")
      (node (ref "J_POW10") (pin "2") (pinfunction "2_2") (pintype "passive"))
      (node (ref "J_POW11") (pin "1") (pinfunction "1_1") (pintype "passive"))
      (node (ref "OK15") (pin "4") (pinfunction "COL_4") (pintype "passive"))
      (node (ref "X15") (pin "1") (pinfunction "KL_1") (pintype "passive"))
    )
    (net (code "93") (name "Net-(OK15-EMIT)") (class "Default")
      (node (ref "OK15") (pin "3") (pinfunction "EMIT_3") (pintype "passive"))
      (node (ref "R50") (pin "1") (pinfunction "1_1") (pintype "passive"))
      (node (ref "R51") (pin "1") (pinfunction "1_1") (pintype "passive"))
      (node (ref "R52") (pin "1") (pinfunction "1_1") (pintype "passive"))
    )
    (net (code "94") (name "Net-(OK16-A)") (class "Default")
      (node (ref "OK16") (pin "1") (pinfunction "A_1") (pintype "passive"))
      (node (ref "R50") (pin "2") (pinfunction "2_2") (pintype "passive"))
    )
    (net (code "95") (name "Net-(OK16-C)") (class "Default")
      (node (ref "OK16") (pin "2") (pinfunction "C_2") (pintype "passive"))
      (node (ref "T12") (pin "C") (pinfunction "C_C") (pintype "passive"))
    )
    (net (code "96") (name "Net-(OK17-A)") (class "Default")
      (node (ref "OK17") (pin "1") (pinfunction "A_1") (pintype "passive"))
      (node (ref "R54") (pin "1") (pinfunction "1_1") (pintype "passive"))
    )
    (net (code "97") (name "Net-(OK17-C)") (class "Default")
      (node (ref "OK17") (pin "2") (pinfunction "C_2") (pintype "passive"))
      (node (ref "T13") (pin "C") (pinfunction "C_C") (pintype "passive"))
    )
    (net (code "98") (name "Net-(OK17-COL)") (class "Default")
      (node (ref "J_POW11") (pin "2") (pinfunction "2_2") (pintype "passive"))
      (node (ref "J_POW13") (pin "1") (pinfunction "1_1") (pintype "passive"))
      (node (ref "OK17") (pin "4") (pinfunction "COL_4") (pintype "passive"))
      (node (ref "X17") (pin "1") (pinfunction "KL_1") (pintype "passive"))
    )
    (net (code "99") (name "Net-(OK17-EMIT)") (class "Default")
      (node (ref "OK17") (pin "3") (pinfunction "EMIT_3") (pintype "passive"))
      (node (ref "R56") (pin "1") (pinfunction "1_1") (pintype "passive"))
      (node (ref "R57") (pin "1") (pinfunction "1_1") (pintype "passive"))
      (node (ref "R58") (pin "1") (pinfunction "1_1") (pintype "passive"))
    )
    (net (code "100") (name "Net-(OK18-A)") (class "Default")
      (node (ref "OK18") (pin "1") (pinfunction "A_1") (pintype "passive"))
      (node (ref "R56") (pin "2") (pinfunction "2_2") (pintype "passive"))
    )
    (net (code "101") (name "Net-(OK18-C)") (class "Default")
      (node (ref "OK18") (pin "2") (pinfunction "C_2") (pintype "passive"))
      (node (ref "T14") (pin "C") (pinfunction "C_C") (pintype "passive"))
    )
    (net (code "102") (name "Net-(OK19-A)") (class "Default")
      (node (ref "OK19") (pin "1") (pinfunction "A_1") (pintype "passive"))
      (node (ref "R60") (pin "1") (pinfunction "1_1") (pintype "passive"))
    )
    (net (code "103") (name "Net-(OK19-C)") (class "Default")
      (node (ref "OK19") (pin "2") (pinfunction "C_2") (pintype "passive"))
      (node (ref "T15") (pin "C") (pinfunction "C_C") (pintype "passive"))
    )
    (net (code "104") (name "Net-(OK19-COL)") (class "Default")
      (node (ref "J_POW13") (pin "2") (pinfunction "2_2") (pintype "passive"))
      (node (ref "OK19") (pin "4") (pinfunction "COL_4") (pintype "passive"))
      (node (ref "X16") (pin "1") (pinfunction "KL_1") (pintype "passive"))
    )
    (net (code "105") (name "Net-(OK19-EMIT)") (class "Default")
      (node (ref "OK19") (pin "3") (pinfunction "EMIT_3") (pintype "passive"))
      (node (ref "R62") (pin "1") (pinfunction "1_1") (pintype "passive"))
      (node (ref "R63") (pin "1") (pinfunction "1_1") (pintype "passive"))
      (node (ref "R64") (pin "1") (pinfunction "1_1") (pintype "passive"))
    )
    (net (code "106") (name "Net-(OK20-A)") (class "Default")
      (node (ref "OK20") (pin "1") (pinfunction "A_1") (pintype "passive"))
      (node (ref "R62") (pin "2") (pinfunction "2_2") (pintype "passive"))
    )
    (net (code "107") (name "Net-(OK20-C)") (class "Default")
      (node (ref "OK20") (pin "2") (pinfunction "C_2") (pintype "passive"))
      (node (ref "T16") (pin "C") (pinfunction "C_C") (pintype "passive"))
    )
    (net (code "108") (name "Net-(Q1-PadB)") (class "Default")
      (node (ref "Q1") (pin "B") (pinfunction "B_B") (pintype "passive"))
      (node (ref "R28") (pin "1") (pinfunction "1_1") (pintype "passive"))
    )
    (net (code "109") (name "Net-(Q2-PadB)") (class "Default")
      (node (ref "Q2") (pin "B") (pinfunction "B_B") (pintype "passive"))
      (node (ref "R32") (pin "1") (pinfunction "1_1") (pintype "passive"))
    )
    (net (code "110") (name "Net-(Q3-PadB)") (class "Default")
      (node (ref "Q3") (pin "B") (pinfunction "B_B") (pintype "passive"))
      (node (ref "R36") (pin "1") (pinfunction "1_1") (pintype "passive"))
    )
    (net (code "111") (name "Net-(Q4-PadB)") (class "Default")
      (node (ref "Q4") (pin "B") (pinfunction "B_B") (pintype "passive"))
      (node (ref "R40") (pin "1") (pinfunction "1_1") (pintype "passive"))
    )
    (net (code "112") (name "Net-(R1-Pad1)") (class "Default")
      (node (ref "R1") (pin "1") (pinfunction "1_1") (pintype "passive"))
      (node (ref "R83") (pin "2") (pinfunction "2_2") (pintype "passive"))
    )
    (net (code "113") (name "Net-(R4-Pad1)") (class "Default")
      (node (ref "R4") (pin "1") (pinfunction "1_1") (pintype "passive"))
      (node (ref "T1") (pin "B") (pinfunction "B_B") (pintype "passive"))
    )
    (net (code "114") (name "Net-(R7-Pad1)") (class "Default")
      (node (ref "R7") (pin "1") (pinfunction "1_1") (pintype "passive"))
      (node (ref "T2") (pin "B") (pinfunction "B_B") (pintype "passive"))
    )
    (net (code "115") (name "Net-(R10-Pad1)") (class "Default")
      (node (ref "R10") (pin "1") (pinfunction "1_1") (pintype "passive"))
      (node (ref "T3") (pin "B") (pinfunction "B_B") (pintype "passive"))
    )
    (net (code "116") (name "Net-(R13-Pad1)") (class "Default")
      (node (ref "R13") (pin "1") (pinfunction "1_1") (pintype "passive"))
      (node (ref "T4") (pin "B") (pinfunction "B_B") (pintype "passive"))
    )
    (net (code "117") (name "Net-(R17-Pad1)") (class "Default")
      (node (ref "R17") (pin "1") (pinfunction "1_1") (pintype "passive"))
      (node (ref "T5") (pin "B") (pinfunction "B_B") (pintype "passive"))
    )
    (net (code "118") (name "Net-(R20-Pad1)") (class "Default")
      (node (ref "R20") (pin "1") (pinfunction "1_1") (pintype "passive"))
      (node (ref "T6") (pin "B") (pinfunction "B_B") (pintype "passive"))
    )
    (net (code "119") (name "Net-(R23-Pad1)") (class "Default")
      (node (ref "R23") (pin "1") (pinfunction "1_1") (pintype "passive"))
      (node (ref "T7") (pin "B") (pinfunction "B_B") (pintype "passive"))
    )
    (net (code "120") (name "Net-(R26-Pad1)") (class "Default")
      (node (ref "R26") (pin "1") (pinfunction "1_1") (pintype "passive"))
      (node (ref "T8") (pin "B") (pinfunction "B_B") (pintype "passive"))
    )
    (net (code "121") (name "Net-(R43-Pad1)") (class "Default")
      (node (ref "R43") (pin "1") (pinfunction "1_1") (pintype "passive"))
      (node (ref "T9") (pin "B") (pinfunction "B_B") (pintype "passive"))
    )
    (net (code "122") (name "Net-(R45-Pad2)") (class "Default")
      (node (ref "R45") (pin "2") (pinfunction "2_2") (pintype "passive"))
      (node (ref "T10") (pin "B") (pinfunction "B_B") (pintype "passive"))
    )
    (net (code "123") (name "Net-(R49-Pad1)") (class "Default")
      (node (ref "R49") (pin "1") (pinfunction "1_1") (pintype "passive"))
      (node (ref "T11") (pin "B") (pinfunction "B_B") (pintype "passive"))
    )
    (net (code "124") (name "Net-(R51-Pad2)") (class "Default")
      (node (ref "R51") (pin "2") (pinfunction "2_2") (pintype "passive"))
      (node (ref "T12") (pin "B") (pinfunction "B_B") (pintype "passive"))
    )
    (net (code "125") (name "Net-(R55-Pad1)") (class "Default")
      (node (ref "R55") (pin "1") (pinfunction "1_1") (pintype "passive"))
      (node (ref "T13") (pin "B") (pinfunction "B_B") (pintype "passive"))
    )
    (net (code "126") (name "Net-(R57-Pad2)") (class "Default")
      (node (ref "R57") (pin "2") (pinfunction "2_2") (pintype "passive"))
      (node (ref "T14") (pin "B") (pinfunction "B_B") (pintype "passive"))
    )
    (net (code "127") (name "Net-(R61-Pad1)") (class "Default")
      (node (ref "R61") (pin "1") (pinfunction "1_1") (pintype "passive"))
      (node (ref "T15") (pin "B") (pinfunction "B_B") (pintype "passive"))
    )
    (net (code "128") (name "Net-(R63-Pad2)") (class "Default")
      (node (ref "R63") (pin "2") (pinfunction "2_2") (pintype "passive"))
      (node (ref "T16") (pin "B") (pinfunction "B_B") (pintype "passive"))
    )
    (net (code "129") (name "Net-(R66-Pad1)") (class "Default")
      (node (ref "R66") (pin "1") (pinfunction "1_1") (pintype "passive"))
      (node (ref "R78") (pin "2") (pinfunction "2_2") (pintype "passive"))
    )
    (net (code "130") (name "Net-(R68-Pad1)") (class "Default")
      (node (ref "R68") (pin "1") (pinfunction "1_1") (pintype "passive"))
      (node (ref "R79") (pin "2") (pinfunction "2_2") (pintype "passive"))
    )
    (net (code "131") (name "Net-(X2C-KL)") (class "Default")
      (node (ref "J_GND") (pin "1") (pinfunction "1_1") (pintype "passive"))
      (node (ref "R3") (pin "1") (pinfunction "1_1") (pintype "passive"))
      (node (ref "X2") (pin "3") (pinfunction "KL_3") (pintype "passive"))
    )
    (net (code "132") (name "Net-(X3C-KL)") (class "Default")
      (node (ref "J_GND") (pin "2") (pinfunction "2_2") (pintype "passive"))
      (node (ref "J_GND1") (pin "1") (pinfunction "1_1") (pintype "passive"))
      (node (ref "R6") (pin "1") (pinfunction "1_1") (pintype "passive"))
      (node (ref "X3") (pin "3") (pinfunction "KL_3") (pintype "passive"))
    )
    (net (code "133") (name "Net-(X4C-KL)") (class "Default")
      (node (ref "J_GND1") (pin "2") (pinfunction "2_2") (pintype "passive"))
      (node (ref "J_GND2") (pin "1") (pinfunction "1_1") (pintype "passive"))
      (node (ref "R9") (pin "1") (pinfunction "1_1") (pintype "passive"))
      (node (ref "X4") (pin "3") (pinfunction "KL_3") (pintype "passive"))
    )
    (net (code "134") (name "Net-(X5C-KL)") (class "Default")
      (node (ref "J_GND2") (pin "2") (pinfunction "2_2") (pintype "passive"))
      (node (ref "J_GND3") (pin "1") (pinfunction "1_1") (pintype "passive"))
      (node (ref "R12") (pin "1") (pinfunction "1_1") (pintype "passive"))
      (node (ref "X5") (pin "3") (pinfunction "KL_3") (pintype "passive"))
    )
    (net (code "135") (name "Net-(X6C-KL)") (class "Default")
      (node (ref "J_GND3") (pin "2") (pinfunction "2_2") (pintype "passive"))
      (node (ref "J_GND5") (pin "2") (pinfunction "2_2") (pintype "passive"))
      (node (ref "R25") (pin "1") (pinfunction "1_1") (pintype "passive"))
      (node (ref "X6") (pin "3") (pinfunction "KL_3") (pintype "passive"))
    )
    (net (code "136") (name "Net-(X7C-KL)") (class "Default")
      (node (ref "J_GND5") (pin "1") (pinfunction "1_1") (pintype "passive"))
      (node (ref "J_GND6") (pin "2") (pinfunction "2_2") (pintype "passive"))
      (node (ref "R22") (pin "1") (pinfunction "1_1") (pintype "passive"))
      (node (ref "X7") (pin "3") (pinfunction "KL_3") (pintype "passive"))
    )
    (net (code "137") (name "Net-(X8C-KL)") (class "Default")
      (node (ref "J_GND6") (pin "1") (pinfunction "1_1") (pintype "passive"))
      (node (ref "J_GND7") (pin "2") (pinfunction "2_2") (pintype "passive"))
      (node (ref "R19") (pin "1") (pinfunction "1_1") (pintype "passive"))
      (node (ref "X8") (pin "3") (pinfunction "KL_3") (pintype "passive"))
    )
    (net (code "138") (name "Net-(X9C-KL)") (class "Default")
      (node (ref "J_GND7") (pin "1") (pinfunction "1_1") (pintype "passive"))
      (node (ref "R16") (pin "1") (pinfunction "1_1") (pintype "passive"))
      (node (ref "X9") (pin "3") (pinfunction "KL_3") (pintype "passive"))
    )
    (net (code "139") (name "Net-(X10A-KL)") (class "Default")
      (node (ref "J_POW4") (pin "1") (pinfunction "1_1") (pintype "passive"))
      (node (ref "R14") (pin "2") (pinfunction "2_2") (pintype "passive"))
      (node (ref "R27") (pin "1") (pinfunction "1_1") (pintype "passive"))
      (node (ref "X10") (pin "1") (pinfunction "KL_1") (pintype "passive"))
    )
    (net (code "140") (name "Net-(X10C-KL)") (class "Default")
      (node (ref "J_GND4") (pin "1") (pinfunction "1_1") (pintype "passive"))
      (node (ref "Q1") (pin "E") (pinfunction "E_E") (pintype "passive"))
      (node (ref "X10") (pin "3") (pinfunction "KL_3") (pintype "passive"))
    )
    (net (code "141") (name "Net-(X11A-KL)") (class "Default")
      (node (ref "J_POW4") (pin "2") (pinfunction "2_2") (pintype "passive"))
      (node (ref "J_POW8") (pin "1") (pinfunction "1_1") (pintype "passive"))
      (node (ref "R30") (pin "2") (pinfunction "2_2") (pintype "passive"))
      (node (ref "R31") (pin "1") (pinfunction "1_1") (pintype "passive"))
      (node (ref "X11") (pin "1") (pinfunction "KL_1") (pintype "passive"))
    )
    (net (code "142") (name "Net-(X11C-KL)") (class "Default")
      (node (ref "J_GND4") (pin "2") (pinfunction "2_2") (pintype "passive"))
      (node (ref "J_GND8") (pin "1") (pinfunction "1_1") (pintype "passive"))
      (node (ref "Q2") (pin "E") (pinfunction "E_E") (pintype "passive"))
      (node (ref "X11") (pin "3") (pinfunction "KL_3") (pintype "passive"))
    )
    (net (code "143") (name "Net-(X12A-KL)") (class "Default")
      (node (ref "J_POW8") (pin "2") (pinfunction "2_2") (pintype "passive"))
      (node (ref "J_POW9") (pin "1") (pinfunction "1_1") (pintype "passive"))
      (node (ref "R34") (pin "2") (pinfunction "2_2") (pintype "passive"))
      (node (ref "R35") (pin "1") (pinfunction "1_1") (pintype "passive"))
      (node (ref "X12") (pin "1") (pinfunction "KL_1") (pintype "passive"))
    )
    (net (code "144") (name "Net-(X12C-KL)") (class "Default")
      (node (ref "J_GND8") (pin "2") (pinfunction "2_2") (pintype "passive"))
      (node (ref "J_GND9") (pin "1") (pinfunction "1_1") (pintype "passive"))
      (node (ref "Q3") (pin "E") (pinfunction "E_E") (pintype "passive"))
      (node (ref "X12") (pin "3") (pinfunction "KL_3") (pintype "passive"))
    )
    (net (code "145") (name "Net-(X13A-KL)") (class "Default")
      (node (ref "J_POW9") (pin "2") (pinfunction "2_2") (pintype "passive"))
      (node (ref "R38") (pin "2") (pinfunction "2_2") (pintype "passive"))
      (node (ref "R39") (pin "1") (pinfunction "1_1") (pintype "passive"))
      (node (ref "X13") (pin "1") (pinfunction "KL_1") (pintype "passive"))
    )
    (net (code "146") (name "Net-(X13C-KL)") (class "Default")
      (node (ref "J_GND9") (pin "2") (pinfunction "2_2") (pintype "passive"))
      (node (ref "Q4") (pin "E") (pinfunction "E_E") (pintype "passive"))
      (node (ref "X13") (pin "3") (pinfunction "KL_3") (pintype "passive"))
    )
    (net (code "147") (name "Net-(X14C-KL)") (class "Default")
      (node (ref "J_GND10") (pin "1") (pinfunction "1_1") (pintype "passive"))
      (node (ref "T10") (pin "E") (pinfunction "E_E") (pintype "passive"))
      (node (ref "X14") (pin "3") (pinfunction "KL_3") (pintype "passive"))
    )
    (net (code "148") (name "Net-(X15C-KL)") (class "Default")
      (node (ref "J_GND10") (pin "2") (pinfunction "2_2") (pintype "passive"))
      (node (ref "J_GND11") (pin "1") (pinfunction "1_1") (pintype "passive"))
      (node (ref "T12") (pin "E") (pinfunction "E_E") (pintype "passive"))
      (node (ref "X15") (pin "3") (pinfunction "KL_3") (pintype "passive"))
    )
    (net (code "149") (name "Net-(X16C-KL)") (class "Default")
      (node (ref "J_GND13") (pin "2") (pinfunction "2_2") (pintype "passive"))
      (node (ref "T16") (pin "E") (pinfunction "E_E") (pintype "passive"))
      (node (ref "X16") (pin "3") (pinfunction "KL_3") (pintype "passive"))
    )
    (net (code "150") (name "Net-(X17C-KL)") (class "Default")
      (node (ref "J_GND11") (pin "2") (pinfunction "2_2") (pintype "passive"))
      (node (ref "J_GND13") (pin "1") (pinfunction "1_1") (pintype "passive"))
      (node (ref "T14") (pin "E") (pinfunction "E_E") (pintype "passive"))
      (node (ref "X17") (pin "3") (pinfunction "KL_3") (pintype "passive"))
    )
    (net (code "151") (name "Net-(X19B-KL)") (class "Default")
      (node (ref "D2") (pin "A") (pinfunction "A_A") (pintype "passive"))
      (node (ref "X19") (pin "2") (pinfunction "KL_2") (pintype "passive"))
    )
    (net (code "152") (name "OUT_0") (class "Default")
      (node (ref "OK1") (pin "3") (pinfunction "EMIT_3") (pintype "passive"))
      (node (ref "R3") (pin "2") (pinfunction "2_2") (pintype "passive"))
      (node (ref "X2") (pin "2") (pinfunction "KL_2") (pintype "passive"))
    )
    (net (code "153") (name "OUT_1") (class "Default")
      (node (ref "OK2") (pin "3") (pinfunction "EMIT_3") (pintype "passive"))
      (node (ref "R6") (pin "2") (pinfunction "2_2") (pintype "passive"))
      (node (ref "X3") (pin "2") (pinfunction "KL_2") (pintype "passive"))
    )
    (net (code "154") (name "OUT_2") (class "Default")
      (node (ref "OK3") (pin "3") (pinfunction "EMIT_3") (pintype "passive"))
      (node (ref "R9") (pin "2") (pinfunction "2_2") (pintype "passive"))
      (node (ref "X4") (pin "2") (pinfunction "KL_2") (pintype "passive"))
    )
    (net (code "155") (name "OUT_3") (class "Default")
      (node (ref "OK4") (pin "3") (pinfunction "EMIT_3") (pintype "passive"))
      (node (ref "R12") (pin "2") (pinfunction "2_2") (pintype "passive"))
      (node (ref "X5") (pin "2") (pinfunction "KL_2") (pintype "passive"))
    )
    (net (code "156") (name "OUT_4") (class "Default")
      (node (ref "OK5") (pin "3") (pinfunction "EMIT_3") (pintype "passive"))
      (node (ref "R16") (pin "2") (pinfunction "2_2") (pintype "passive"))
      (node (ref "X9") (pin "2") (pinfunction "KL_2") (pintype "passive"))
    )
    (net (code "157") (name "OUT_5") (class "Default")
      (node (ref "OK6") (pin "3") (pinfunction "EMIT_3") (pintype "passive"))
      (node (ref "R19") (pin "2") (pinfunction "2_2") (pintype "passive"))
      (node (ref "X8") (pin "2") (pinfunction "KL_2") (pintype "passive"))
    )
    (net (code "158") (name "OUT_6") (class "Default")
      (node (ref "OK7") (pin "3") (pinfunction "EMIT_3") (pintype "passive"))
      (node (ref "R22") (pin "2") (pinfunction "2_2") (pintype "passive"))
      (node (ref "X7") (pin "2") (pinfunction "KL_2") (pintype "passive"))
    )
    (net (code "159") (name "OUT_7") (class "Default")
      (node (ref "OK8") (pin "3") (pinfunction "EMIT_3") (pintype "passive"))
      (node (ref "R25") (pin "2") (pinfunction "2_2") (pintype "passive"))
      (node (ref "X6") (pin "2") (pinfunction "KL_2") (pintype "passive"))
    )
    (net (code "160") (name "unconnected-(MALE-Pad24)") (class "Default")
      (node (ref "MALE") (pin "24") (pinfunction "24_24") (pintype "passive"))
    )
    (net (code "161") (name "unconnected-(MALE-Pad26)") (class "Default")
      (node (ref "MALE") (pin "26") (pinfunction "26_26") (pintype "passive"))
    )
    (net (code "162") (name "unconnected-(MALE-Pad28)") (class "Default")
      (node (ref "MALE") (pin "28") (pinfunction "28_28") (pintype "passive"))
    )
    (net (code "163") (name "unconnected-(MALE-Pad29)") (class "Default")
      (node (ref "MALE") (pin "29") (pinfunction "29_29") (pintype "passive"))
    )
    (net (code "164") (name "unconnected-(MALE-Pad30)") (class "Default")
      (node (ref "MALE") (pin "30") (pinfunction "30_30") (pintype "passive"))
    )
    (net (code "165") (name "unconnected-(MALE-Pad31)") (class "Default")
      (node (ref "MALE") (pin "31") (pinfunction "31_31") (pintype "passive"))
    )
    (net (code "166") (name "unconnected-(MALE-Pad32)") (class "Default")
      (node (ref "MALE") (pin "32") (pinfunction "32_32") (pintype "passive"))
    )
  )
)
